# FPGA_APU_V3.net
KiCad netlist of a schematic drawn in EAGLE
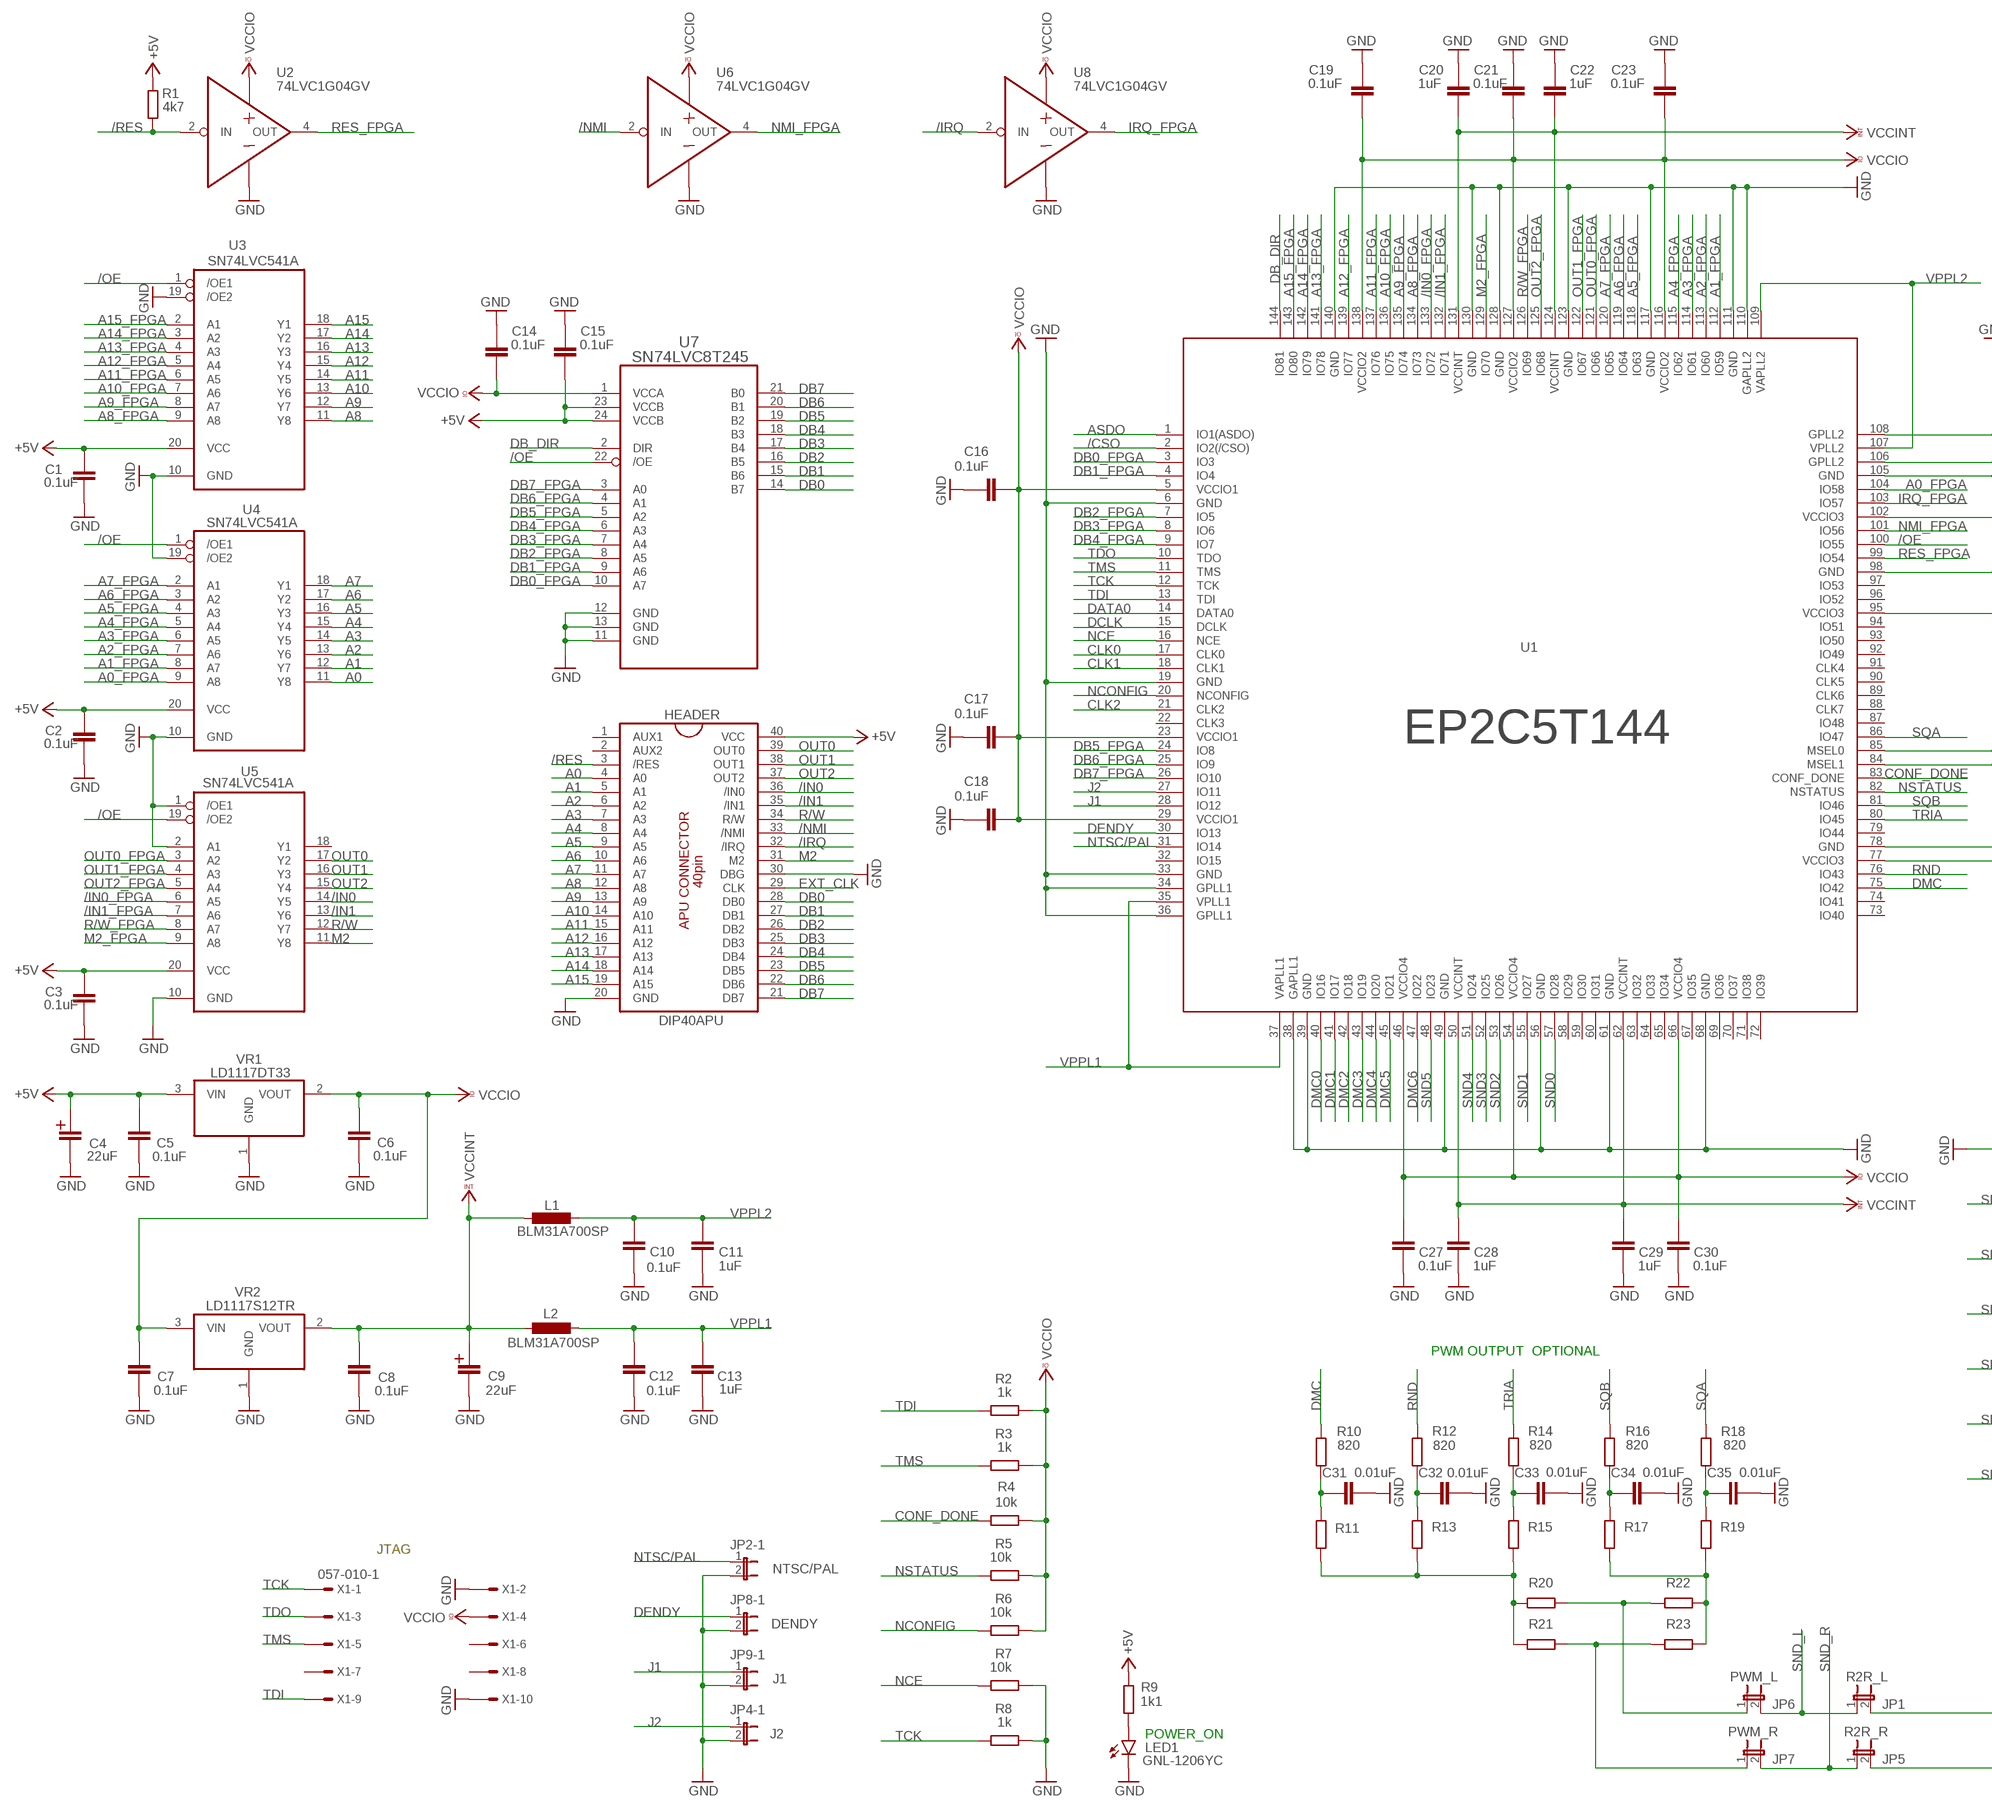
[diagram p0: schematic, sheet 1, part 1 of 2]
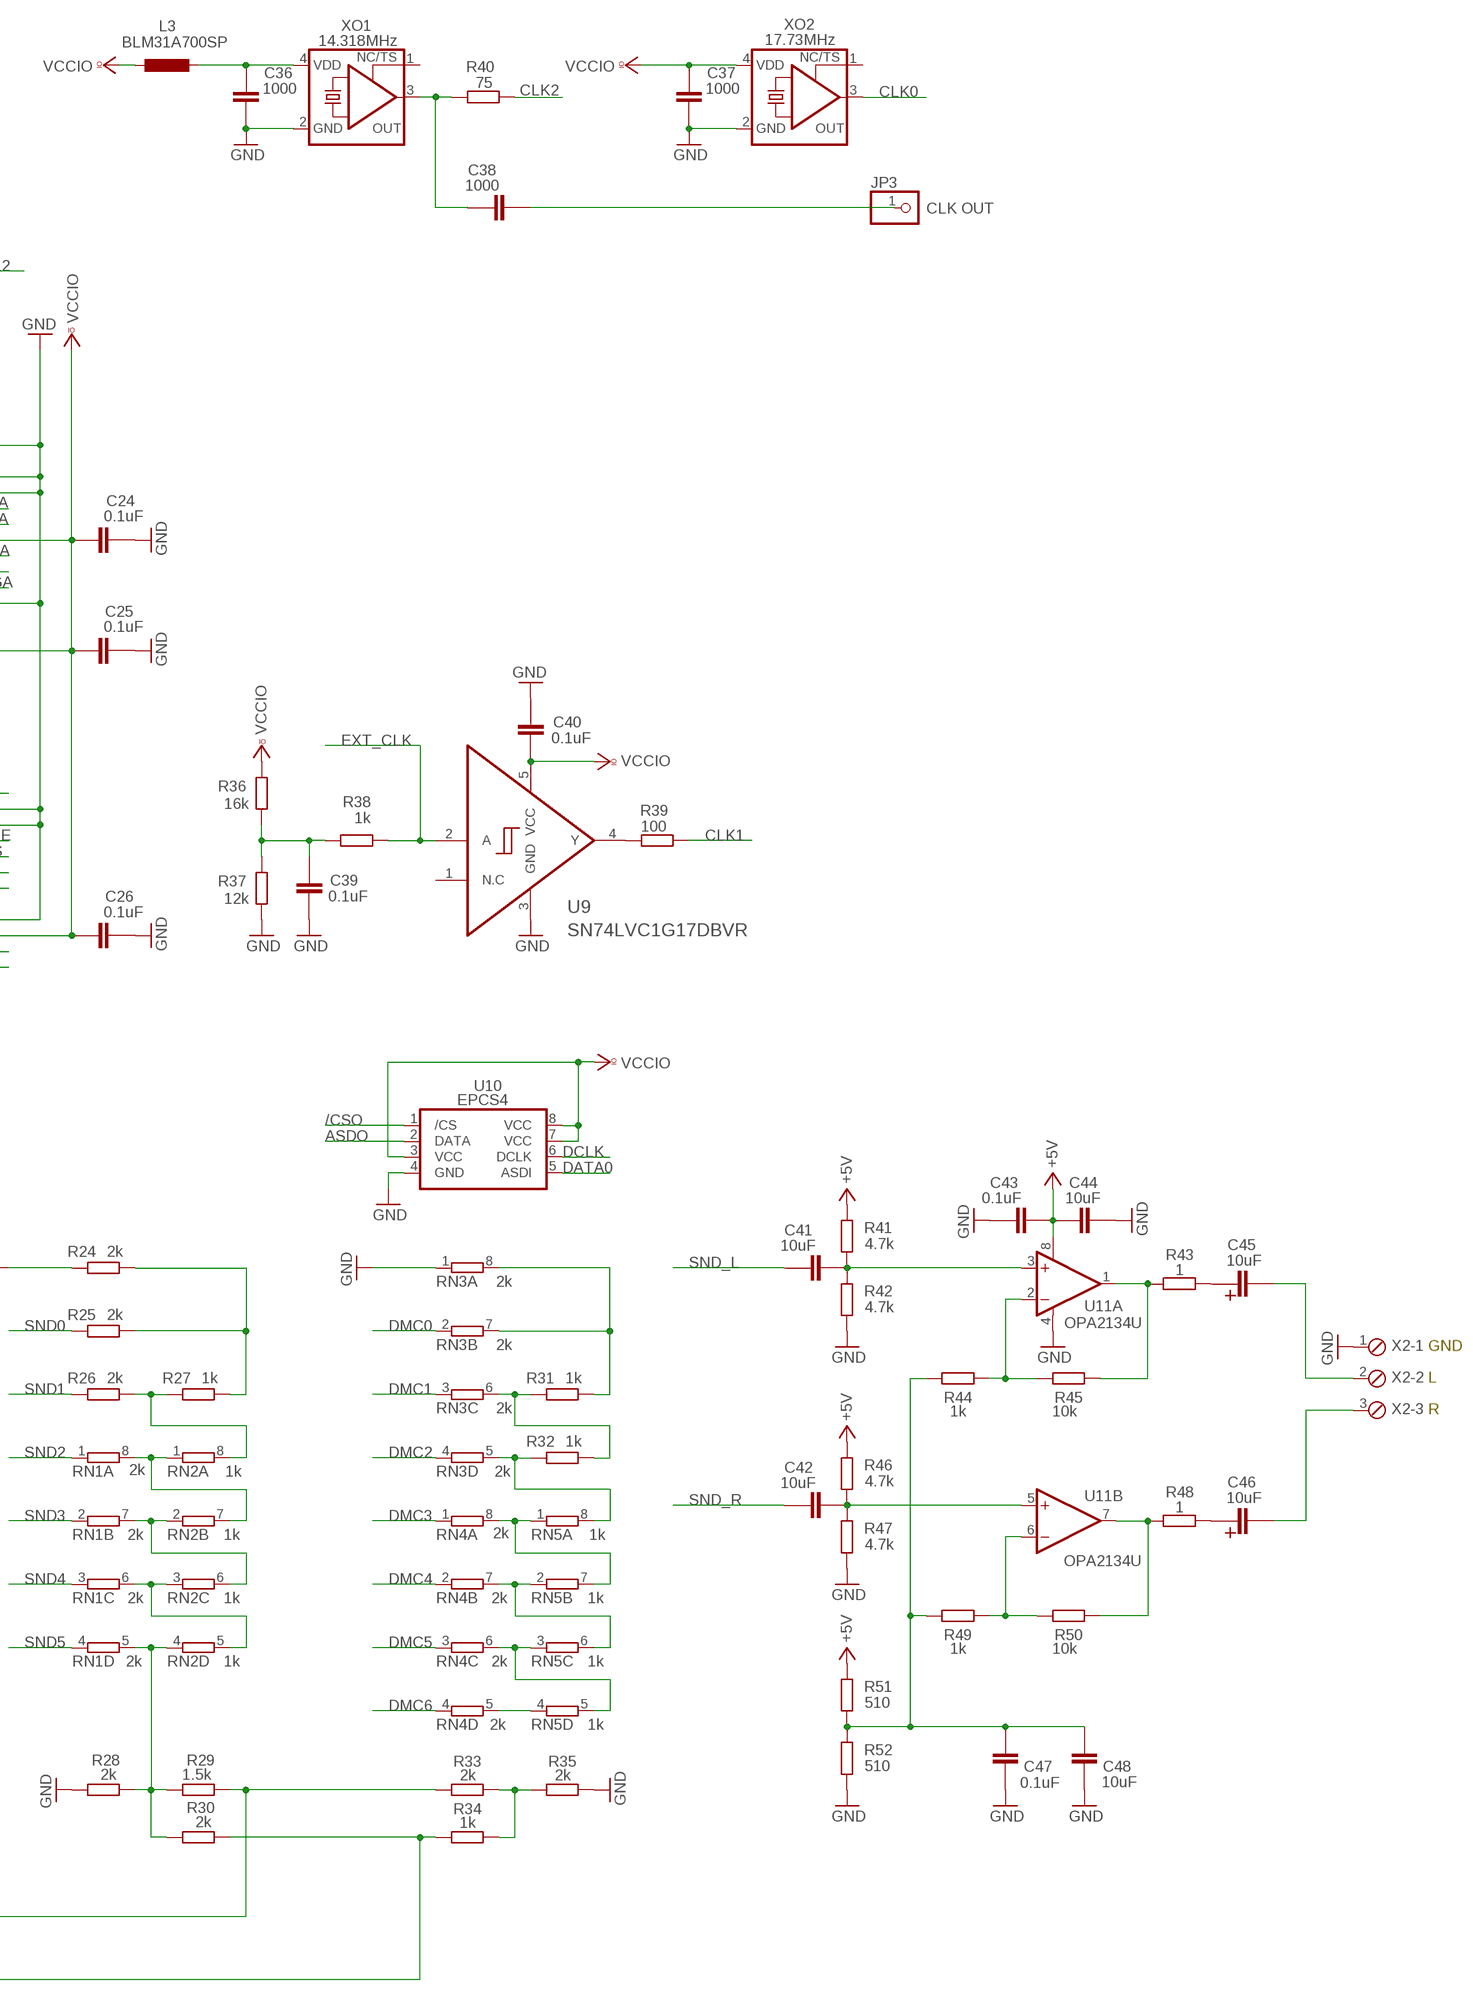
[diagram p1: schematic, sheet 1, part 2 of 2]

(export (version "E")
  (design (tool "Eeschema 10.0.6"))
  (components
    (comp (ref "C1")
      (value "0.1uF")
      (footprint "eagle-import:C0805")
      (libsource (lib "eagle-import") (part "C-EUC0805"))
    )
    (comp (ref "C2")
      (value "0.1uF")
      (footprint "eagle-import:C0805")
      (libsource (lib "eagle-import") (part "C-EUC0805"))
    )
    (comp (ref "C3")
      (value "0.1uF")
      (footprint "eagle-import:C0805")
      (libsource (lib "eagle-import") (part "C-EUC0805"))
    )
    (comp (ref "C4")
      (value "22uF")
      (footprint "eagle-import:153CLV-0505")
      (libsource (lib "eagle-import") (part "CPOL-EU153CLV-0505"))
    )
    (comp (ref "C5")
      (value "0.1uF")
      (footprint "eagle-import:C0805")
      (libsource (lib "eagle-import") (part "C-EUC0805"))
    )
    (comp (ref "C6")
      (value "0.1uF")
      (footprint "eagle-import:C0805")
      (libsource (lib "eagle-import") (part "C-EUC0805"))
    )
    (comp (ref "C7")
      (value "0.1uF")
      (footprint "eagle-import:C0805")
      (libsource (lib "eagle-import") (part "C-EUC0805"))
    )
    (comp (ref "C8")
      (value "0.1uF")
      (footprint "eagle-import:C0805")
      (libsource (lib "eagle-import") (part "C-EUC0805"))
    )
    (comp (ref "C9")
      (value "22uF")
      (footprint "eagle-import:153CLV-0505")
      (libsource (lib "eagle-import") (part "CPOL-EU153CLV-0505"))
    )
    (comp (ref "C10")
      (value "0.1uF")
      (footprint "eagle-import:C0805")
      (libsource (lib "eagle-import") (part "C-EUC0805"))
    )
    (comp (ref "C11")
      (value "1uF")
      (footprint "eagle-import:C0805")
      (libsource (lib "eagle-import") (part "C-EUC0805"))
    )
    (comp (ref "C12")
      (value "0.1uF")
      (footprint "eagle-import:C0805")
      (libsource (lib "eagle-import") (part "C-EUC0805"))
    )
    (comp (ref "C13")
      (value "1uF")
      (footprint "eagle-import:C0805")
      (libsource (lib "eagle-import") (part "C-EUC0805"))
    )
    (comp (ref "C14")
      (value "0.1uF")
      (footprint "eagle-import:C0805")
      (libsource (lib "eagle-import") (part "C-EUC0805"))
    )
    (comp (ref "C15")
      (value "0.1uF")
      (footprint "eagle-import:C0805")
      (libsource (lib "eagle-import") (part "C-EUC0805"))
    )
    (comp (ref "C16")
      (value "0.1uF")
      (footprint "eagle-import:C0805")
      (libsource (lib "eagle-import") (part "C-EUC0805"))
    )
    (comp (ref "C17")
      (value "0.1uF")
      (footprint "eagle-import:C0805")
      (libsource (lib "eagle-import") (part "C-EUC0805"))
    )
    (comp (ref "C18")
      (value "0.1uF")
      (footprint "eagle-import:C0805")
      (libsource (lib "eagle-import") (part "C-EUC0805"))
    )
    (comp (ref "C19")
      (value "0.1uF")
      (footprint "eagle-import:C0805")
      (libsource (lib "eagle-import") (part "C-EUC0805"))
    )
    (comp (ref "C20")
      (value "1uF")
      (footprint "eagle-import:C0805")
      (libsource (lib "eagle-import") (part "C-EUC0805"))
    )
    (comp (ref "C21")
      (value "0.1uF")
      (footprint "eagle-import:C0805")
      (libsource (lib "eagle-import") (part "C-EUC0805"))
    )
    (comp (ref "C22")
      (value "1uF")
      (footprint "eagle-import:C0805")
      (libsource (lib "eagle-import") (part "C-EUC0805"))
    )
    (comp (ref "C23")
      (value "0.1uF")
      (footprint "eagle-import:C0805")
      (libsource (lib "eagle-import") (part "C-EUC0805"))
    )
    (comp (ref "C24")
      (value "0.1uF")
      (footprint "eagle-import:C0805")
      (libsource (lib "eagle-import") (part "C-EUC0805"))
    )
    (comp (ref "C25")
      (value "0.1uF")
      (footprint "eagle-import:C0805")
      (libsource (lib "eagle-import") (part "C-EUC0805"))
    )
    (comp (ref "C26")
      (value "0.1uF")
      (footprint "eagle-import:C0805")
      (libsource (lib "eagle-import") (part "C-EUC0805"))
    )
    (comp (ref "C27")
      (value "0.1uF")
      (footprint "eagle-import:C0805")
      (libsource (lib "eagle-import") (part "C-EUC0805"))
    )
    (comp (ref "C28")
      (value "1uF")
      (footprint "eagle-import:C0805")
      (libsource (lib "eagle-import") (part "C-EUC0805"))
    )
    (comp (ref "C29")
      (value "1uF")
      (footprint "eagle-import:C0805")
      (libsource (lib "eagle-import") (part "C-EUC0805"))
    )
    (comp (ref "C30")
      (value "0.1uF")
      (footprint "eagle-import:C0805")
      (libsource (lib "eagle-import") (part "C-EUC0805"))
    )
    (comp (ref "C31")
      (value "0.01uF")
      (footprint "eagle-import:C0805")
      (libsource (lib "eagle-import") (part "C-EUC0805"))
    )
    (comp (ref "C32")
      (value "0.01uF")
      (footprint "eagle-import:C0805")
      (libsource (lib "eagle-import") (part "C-EUC0805"))
    )
    (comp (ref "C33")
      (value "0.01uF")
      (footprint "eagle-import:C0805")
      (libsource (lib "eagle-import") (part "C-EUC0805"))
    )
    (comp (ref "C34")
      (value "0.01uF")
      (footprint "eagle-import:C0805")
      (libsource (lib "eagle-import") (part "C-EUC0805"))
    )
    (comp (ref "C35")
      (value "0.01uF")
      (footprint "eagle-import:C0805")
      (libsource (lib "eagle-import") (part "C-EUC0805"))
    )
    (comp (ref "C36")
      (value "1000")
      (footprint "eagle-import:C0805")
      (libsource (lib "eagle-import") (part "C-EUC0805"))
    )
    (comp (ref "C37")
      (value "1000")
      (footprint "eagle-import:C0805")
      (libsource (lib "eagle-import") (part "C-EUC0805"))
    )
    (comp (ref "C38")
      (value "1000")
      (footprint "eagle-import:C0805")
      (libsource (lib "eagle-import") (part "C-EUC0805"))
    )
    (comp (ref "C39")
      (value "0.1uF")
      (footprint "eagle-import:C0603")
      (libsource (lib "eagle-import") (part "C-EUC0603"))
    )
    (comp (ref "C40")
      (value "0.1uF")
      (footprint "eagle-import:C0603")
      (libsource (lib "eagle-import") (part "C-EUC0603"))
    )
    (comp (ref "C41")
      (value "10uF")
      (footprint "eagle-import:C0805")
      (libsource (lib "eagle-import") (part "C-EUC0805"))
    )
    (comp (ref "C42")
      (value "10uF")
      (footprint "eagle-import:C0805")
      (libsource (lib "eagle-import") (part "C-EUC0805"))
    )
    (comp (ref "C43")
      (value "0.1uF")
      (footprint "eagle-import:C0805")
      (libsource (lib "eagle-import") (part "C-EUC0805"))
    )
    (comp (ref "C44")
      (value "10uF")
      (footprint "eagle-import:C0805")
      (libsource (lib "eagle-import") (part "C-EUC0805"))
    )
    (comp (ref "C45")
      (value "10uF")
      (footprint "eagle-import:153CLV-0505")
      (libsource (lib "eagle-import") (part "CPOL-EU153CLV-0505"))
    )
    (comp (ref "C46")
      (value "10uF")
      (footprint "eagle-import:153CLV-0505")
      (libsource (lib "eagle-import") (part "CPOL-EU153CLV-0505"))
    )
    (comp (ref "C47")
      (value "0.1uF")
      (footprint "eagle-import:C0805")
      (libsource (lib "eagle-import") (part "C-EUC0805"))
    )
    (comp (ref "C48")
      (value "10uF")
      (footprint "eagle-import:C0805")
      (libsource (lib "eagle-import") (part "C-EUC0805"))
    )
    (comp (ref "HEADER")
      (value "DIP40APU")
      (footprint "eagle-import:DIP-40")
      (libsource (lib "eagle-import") (part "DIP40APU"))
    )
    (comp (ref "JP1")
      (value "R2R_L")
      (footprint "eagle-import:JP1")
      (libsource (lib "eagle-import") (part "JP1E"))
    )
    (comp (ref "JP2")
      (value "NTSC/PAL")
      (footprint "eagle-import:JP4Q")
      (libsource (lib "eagle-import") (part "JP4QE"))
    )
    (comp (ref "JP3")
      (value "CLK OUT")
      (footprint "eagle-import:1X01")
      (libsource (lib "eagle-import") (part "PINHD-1X1"))
    )
    (comp (ref "JP4")
      (value "J2")
      (footprint "eagle-import:JP4Q")
      (libsource (lib "eagle-import") (part "JP4QE"))
    )
    (comp (ref "JP5")
      (value "R2R_R")
      (footprint "eagle-import:JP1")
      (libsource (lib "eagle-import") (part "JP1E"))
    )
    (comp (ref "JP6")
      (value "PWM_L")
      (footprint "eagle-import:JP1")
      (libsource (lib "eagle-import") (part "JP1E"))
    )
    (comp (ref "JP7")
      (value "PWM_R")
      (footprint "eagle-import:JP1")
      (libsource (lib "eagle-import") (part "JP1E"))
    )
    (comp (ref "JP8")
      (value "DENDY")
      (footprint "eagle-import:JP4Q")
      (libsource (lib "eagle-import") (part "JP4QE"))
    )
    (comp (ref "JP9")
      (value "J1")
      (footprint "eagle-import:JP4Q")
      (libsource (lib "eagle-import") (part "JP4QE"))
    )
    (comp (ref "L1")
      (value "BLM31A700SP")
      (footprint "eagle-import:L2012C")
      (libsource (lib "eagle-import") (part "L-EUL2012C"))
    )
    (comp (ref "L2")
      (value "BLM31A700SP")
      (footprint "eagle-import:L2012C")
      (libsource (lib "eagle-import") (part "L-EUL2012C"))
    )
    (comp (ref "L3")
      (value "BLM31A700SP")
      (footprint "eagle-import:L2012C")
      (libsource (lib "eagle-import") (part "L-EUL2012C"))
    )
    (comp (ref "LED1")
      (value "GNL-1206YC")
      (footprint "eagle-import:SMARTLED-TTW")
      (libsource (lib "eagle-import") (part "LED"))
    )
    (comp (ref "R1")
      (value "4k7")
      (footprint "eagle-import:R0805")
      (libsource (lib "eagle-import") (part "R-EU_R0805"))
    )
    (comp (ref "R2")
      (value "1k")
      (footprint "eagle-import:R0805")
      (libsource (lib "eagle-import") (part "R-EU_R0805"))
    )
    (comp (ref "R3")
      (value "1k")
      (footprint "eagle-import:R0805")
      (libsource (lib "eagle-import") (part "R-EU_R0805"))
    )
    (comp (ref "R4")
      (value "10k")
      (footprint "eagle-import:R0805")
      (libsource (lib "eagle-import") (part "R-EU_R0805"))
    )
    (comp (ref "R5")
      (value "10k")
      (footprint "eagle-import:R0805")
      (libsource (lib "eagle-import") (part "R-EU_R0805"))
    )
    (comp (ref "R6")
      (value "10k")
      (footprint "eagle-import:R0805")
      (libsource (lib "eagle-import") (part "R-EU_R0805"))
    )
    (comp (ref "R7")
      (value "10k")
      (footprint "eagle-import:R0805")
      (libsource (lib "eagle-import") (part "R-EU_R0805"))
    )
    (comp (ref "R8")
      (value "1k")
      (footprint "eagle-import:R0805")
      (libsource (lib "eagle-import") (part "R-EU_R0805"))
    )
    (comp (ref "R9")
      (value "1k1")
      (footprint "eagle-import:R0805")
      (libsource (lib "eagle-import") (part "R-EU_R0805"))
    )
    (comp (ref "R10")
      (value "820")
      (footprint "eagle-import:R0805")
      (libsource (lib "eagle-import") (part "R-EU_R0805"))
    )
    (comp (ref "R11")
      (value "R-EU_R0805")
      (footprint "eagle-import:R0805")
      (libsource (lib "eagle-import") (part "R-EU_R0805"))
    )
    (comp (ref "R12")
      (value "820")
      (footprint "eagle-import:R0805")
      (libsource (lib "eagle-import") (part "R-EU_R0805"))
    )
    (comp (ref "R13")
      (value "R-EU_R0805")
      (footprint "eagle-import:R0805")
      (libsource (lib "eagle-import") (part "R-EU_R0805"))
    )
    (comp (ref "R14")
      (value "820")
      (footprint "eagle-import:R0805")
      (libsource (lib "eagle-import") (part "R-EU_R0805"))
    )
    (comp (ref "R15")
      (value "R-EU_R0805")
      (footprint "eagle-import:R0805")
      (libsource (lib "eagle-import") (part "R-EU_R0805"))
    )
    (comp (ref "R16")
      (value "820")
      (footprint "eagle-import:R0805")
      (libsource (lib "eagle-import") (part "R-EU_R0805"))
    )
    (comp (ref "R17")
      (value "R-EU_R0805")
      (footprint "eagle-import:R0805")
      (libsource (lib "eagle-import") (part "R-EU_R0805"))
    )
    (comp (ref "R18")
      (value "820")
      (footprint "eagle-import:R0805")
      (libsource (lib "eagle-import") (part "R-EU_R0805"))
    )
    (comp (ref "R19")
      (value "R-EU_R0805")
      (footprint "eagle-import:R0805")
      (libsource (lib "eagle-import") (part "R-EU_R0805"))
    )
    (comp (ref "R20")
      (value "R-EU_R0805")
      (footprint "eagle-import:R0805")
      (libsource (lib "eagle-import") (part "R-EU_R0805"))
    )
    (comp (ref "R21")
      (value "R-EU_R0805")
      (footprint "eagle-import:R0805")
      (libsource (lib "eagle-import") (part "R-EU_R0805"))
    )
    (comp (ref "R22")
      (value "R-EU_R0805")
      (footprint "eagle-import:R0805")
      (libsource (lib "eagle-import") (part "R-EU_R0805"))
    )
    (comp (ref "R23")
      (value "R-EU_R0805")
      (footprint "eagle-import:R0805")
      (libsource (lib "eagle-import") (part "R-EU_R0805"))
    )
    (comp (ref "R24")
      (value "2k")
      (footprint "eagle-import:R0805")
      (libsource (lib "eagle-import") (part "R-EU_R0805"))
    )
    (comp (ref "R25")
      (value "2k")
      (footprint "eagle-import:R0805")
      (libsource (lib "eagle-import") (part "R-EU_R0805"))
    )
    (comp (ref "R26")
      (value "2k")
      (footprint "eagle-import:R0805")
      (libsource (lib "eagle-import") (part "R-EU_R0805"))
    )
    (comp (ref "R27")
      (value "1k")
      (footprint "eagle-import:R0805")
      (libsource (lib "eagle-import") (part "R-EU_R0805"))
    )
    (comp (ref "R28")
      (value "2k")
      (footprint "eagle-import:R0805")
      (libsource (lib "eagle-import") (part "R-EU_R0805"))
    )
    (comp (ref "R29")
      (value "1.5k")
      (footprint "eagle-import:R0805")
      (libsource (lib "eagle-import") (part "R-EU_R0805"))
    )
    (comp (ref "R30")
      (value "2k")
      (footprint "eagle-import:R0805")
      (libsource (lib "eagle-import") (part "R-EU_R0805"))
    )
    (comp (ref "R31")
      (value "1k")
      (footprint "eagle-import:R0805")
      (libsource (lib "eagle-import") (part "R-EU_R0805"))
    )
    (comp (ref "R32")
      (value "1k")
      (footprint "eagle-import:R0805")
      (libsource (lib "eagle-import") (part "R-EU_R0805"))
    )
    (comp (ref "R33")
      (value "2k")
      (footprint "eagle-import:R0805")
      (libsource (lib "eagle-import") (part "R-EU_R0805"))
    )
    (comp (ref "R34")
      (value "1k")
      (footprint "eagle-import:R0805")
      (libsource (lib "eagle-import") (part "R-EU_R0805"))
    )
    (comp (ref "R35")
      (value "2k")
      (footprint "eagle-import:R0805")
      (libsource (lib "eagle-import") (part "R-EU_R0805"))
    )
    (comp (ref "R36")
      (value "16k")
      (footprint "eagle-import:R0805")
      (libsource (lib "eagle-import") (part "R-EU_R0805"))
    )
    (comp (ref "R37")
      (value "12k")
      (footprint "eagle-import:R0805")
      (libsource (lib "eagle-import") (part "R-EU_R0805"))
    )
    (comp (ref "R38")
      (value "1k")
      (footprint "eagle-import:R0805")
      (libsource (lib "eagle-import") (part "R-EU_R0805"))
    )
    (comp (ref "R39")
      (value "100")
      (footprint "eagle-import:R0805")
      (libsource (lib "eagle-import") (part "R-EU_R0805"))
    )
    (comp (ref "R40")
      (value "75")
      (footprint "eagle-import:R0805")
      (libsource (lib "eagle-import") (part "R-EU_R0805"))
    )
    (comp (ref "R41")
      (value "4.7k")
      (footprint "eagle-import:R0805")
      (libsource (lib "eagle-import") (part "R-EU_R0805"))
    )
    (comp (ref "R42")
      (value "4.7k")
      (footprint "eagle-import:R0805")
      (libsource (lib "eagle-import") (part "R-EU_R0805"))
    )
    (comp (ref "R43")
      (value "1")
      (footprint "eagle-import:R0805")
      (libsource (lib "eagle-import") (part "R-EU_R0805"))
    )
    (comp (ref "R44")
      (value "1k")
      (footprint "eagle-import:R0805")
      (libsource (lib "eagle-import") (part "R-EU_R0805"))
    )
    (comp (ref "R45")
      (value "10k")
      (footprint "eagle-import:R0805")
      (libsource (lib "eagle-import") (part "R-EU_R0805"))
    )
    (comp (ref "R46")
      (value "4.7k")
      (footprint "eagle-import:R0805")
      (libsource (lib "eagle-import") (part "R-EU_R0805"))
    )
    (comp (ref "R47")
      (value "4.7k")
      (footprint "eagle-import:R0805")
      (libsource (lib "eagle-import") (part "R-EU_R0805"))
    )
    (comp (ref "R48")
      (value "1")
      (footprint "eagle-import:R0805")
      (libsource (lib "eagle-import") (part "R-EU_R0805"))
    )
    (comp (ref "R49")
      (value "1k")
      (footprint "eagle-import:R0805")
      (libsource (lib "eagle-import") (part "R-EU_R0805"))
    )
    (comp (ref "R50")
      (value "10k")
      (footprint "eagle-import:R0805")
      (libsource (lib "eagle-import") (part "R-EU_R0805"))
    )
    (comp (ref "R51")
      (value "510")
      (footprint "eagle-import:R0805")
      (libsource (lib "eagle-import") (part "R-EU_R0805"))
    )
    (comp (ref "R52")
      (value "510")
      (footprint "eagle-import:R0805")
      (libsource (lib "eagle-import") (part "R-EU_R0805"))
    )
    (comp (ref "RN1")
      (value "2k")
      (footprint "eagle-import:0603-ARC")
      (libsource (lib "eagle-import") (part "4R-N0603-ARC"))
    )
    (comp (ref "RN2")
      (value "1k")
      (footprint "eagle-import:0603-ARC")
      (libsource (lib "eagle-import") (part "4R-N0603-ARC"))
    )
    (comp (ref "RN3")
      (value "2k")
      (footprint "eagle-import:0603-ARC")
      (libsource (lib "eagle-import") (part "4R-N0603-ARC"))
    )
    (comp (ref "RN4")
      (value "2k")
      (footprint "eagle-import:0603-ARC")
      (libsource (lib "eagle-import") (part "4R-N0603-ARC"))
    )
    (comp (ref "RN5")
      (value "1k")
      (footprint "eagle-import:0603-ARC")
      (libsource (lib "eagle-import") (part "4R-N0603-ARC"))
    )
    (comp (ref "U1")
      (value "EP2C5T144")
      (footprint "eagle-import:TQFP144")
      (fields (field (name "MPN") "EP2C5T144C8N"))
      (libsource (lib "eagle-import") (part "EP2C5T144"))
    )
    (comp (ref "U2")
      (value "74LVC1G04GV")
      (footprint "eagle-import:SOT95P275X110-5N")
      (libsource (lib "eagle-import") (part "74LVC1G04GV"))
    )
    (comp (ref "U3")
      (value "SN74LVC541A")
      (footprint "eagle-import:TSOP20")
      (libsource (lib "eagle-import") (part "SN74LVC541A"))
    )
    (comp (ref "U4")
      (value "SN74LVC541A")
      (footprint "eagle-import:TSOP20")
      (libsource (lib "eagle-import") (part "SN74LVC541A"))
    )
    (comp (ref "U5")
      (value "SN74LVC541A")
      (footprint "eagle-import:TSOP20")
      (libsource (lib "eagle-import") (part "SN74LVC541A"))
    )
    (comp (ref "U6")
      (value "74LVC1G04GV")
      (footprint "eagle-import:SOT95P275X110-5N")
      (libsource (lib "eagle-import") (part "74LVC1G04GV"))
    )
    (comp (ref "U7")
      (value "SN74LVC8T245")
      (footprint "eagle-import:SOP65P640X110-24N")
      (libsource (lib "eagle-import") (part "SN74LVC8T245"))
    )
    (comp (ref "U8")
      (value "74LVC1G04GV")
      (footprint "eagle-import:SOT95P275X110-5N")
      (libsource (lib "eagle-import") (part "74LVC1G04GV"))
    )
    (comp (ref "U9")
      (value "SN74LVC1G17DBVR")
      (footprint "eagle-import:SOT95P280X145-5N")
      (libsource (lib "eagle-import") (part "SN74LVC1G17DBVR"))
    )
    (comp (ref "U10")
      (value "EPCS4")
      (footprint "eagle-import:SO08")
      (libsource (lib "eagle-import") (part "EPCS4"))
    )
    (comp (ref "U11")
      (value "OPA2134U")
      (footprint "eagle-import:SO08")
      (fields (field (name "MF") "TEXAS INSTRUMENTS") (field (name "MPN") "OPA2134UA"))
      (libsource (lib "eagle-import") (part "OPA2134U"))
    )
    (comp (ref "VR1")
      (value "LD1117DT33")
      (footprint "eagle-import:DPAK456P1010X240-3N")
      (fields (field (name "MANUFACTURER") "STMicroelectronics"))
      (libsource (lib "eagle-import") (part "LD1117DT33"))
    )
    (comp (ref "VR2")
      (value "LD1117S12TR")
      (footprint "eagle-import:SOT-223-3")
      (libsource (lib "eagle-import") (part "LD1117S12TR"))
    )
    (comp (ref "X1")
      (value "057-010-1")
      (footprint "eagle-import:057-010-1")
      (libsource (lib "eagle-import") (part "057-010-1"))
    )
    (comp (ref "X2")
      (value "OUT")
      (footprint "eagle-import:7POL254")
      (libsource (lib "eagle-import") (part "MPT7"))
    )
    (comp (ref "XO1")
      (value "14.318MHz")
      (footprint "eagle-import:7.0X5.08_KXO-(V)97")
      (libsource (lib "eagle-import") (part "KXO-PXO/XO-V97"))
    )
    (comp (ref "XO2")
      (value "17.73MHz")
      (footprint "eagle-import:2.5X2.0_KXO-V95")
      (libsource (lib "eagle-import") (part "KXO-PXO/XO-V95"))
    )
  )
  (nets
    (net (code "1") (name "+5V") (class "Default")
      (node (ref "C1") (pin "1") (pinfunction "1_1") (pintype "passive"))
      (node (ref "C15") (pin "2") (pinfunction "2_2") (pintype "passive"))
      (node (ref "C2") (pin "1") (pinfunction "1_1") (pintype "passive"))
      (node (ref "C3") (pin "1") (pinfunction "1_1") (pintype "passive"))
      (node (ref "C4") (pin "+") (pinfunction "+_+") (pintype "passive"))
      (node (ref "C43") (pin "2") (pinfunction "2_2") (pintype "passive"))
      (node (ref "C44") (pin "1") (pinfunction "1_1") (pintype "passive"))
      (node (ref "C5") (pin "1") (pinfunction "1_1") (pintype "passive"))
      (node (ref "HEADER") (pin "40") (pinfunction "VCC_40") (pintype "power_in"))
      (node (ref "R1") (pin "1") (pinfunction "1_1") (pintype "passive"))
      (node (ref "R41") (pin "1") (pinfunction "1_1") (pintype "passive"))
      (node (ref "R46") (pin "1") (pinfunction "1_1") (pintype "passive"))
      (node (ref "R51") (pin "1") (pinfunction "1_1") (pintype "passive"))
      (node (ref "R9") (pin "2") (pinfunction "2_2") (pintype "passive"))
      (node (ref "U11") (pin "8") (pinfunction "V+_8") (pintype "power_in"))
      (node (ref "U3") (pin "20") (pinfunction "VCC_20") (pintype "power_in"))
      (node (ref "U4") (pin "20") (pinfunction "VCC_20") (pintype "power_in"))
      (node (ref "U5") (pin "20") (pinfunction "VCC_20") (pintype "power_in"))
      (node (ref "U7") (pin "23") (pinfunction "VCCB_23") (pintype "power_in"))
      (node (ref "U7") (pin "24") (pinfunction "VCCB_24") (pintype "power_in"))
      (node (ref "VR1") (pin "3") (pinfunction "VIN_3") (pintype "power_in"))
    )
    (net (code "2") (name "/A0") (class "Default")
      (node (ref "HEADER") (pin "4") (pinfunction "A0_4") (pintype "input"))
      (node (ref "U4") (pin "11") (pinfunction "Y8_11") (pintype "output"))
    )
    (net (code "3") (name "/A0_FPGA") (class "Default")
      (node (ref "U1") (pin "104") (pinfunction "IO58_104") (pintype "bidirectional"))
      (node (ref "U4") (pin "9") (pinfunction "A8_9") (pintype "input"))
    )
    (net (code "4") (name "/A1") (class "Default")
      (node (ref "HEADER") (pin "5") (pinfunction "A1_5") (pintype "input"))
      (node (ref "U4") (pin "12") (pinfunction "Y7_12") (pintype "output"))
    )
    (net (code "5") (name "/A1_FPGA") (class "Default")
      (node (ref "U1") (pin "112") (pinfunction "IO59_112") (pintype "bidirectional"))
      (node (ref "U4") (pin "8") (pinfunction "A7_8") (pintype "input"))
    )
    (net (code "6") (name "/A2") (class "Default")
      (node (ref "HEADER") (pin "6") (pinfunction "A2_6") (pintype "input"))
      (node (ref "U4") (pin "13") (pinfunction "Y6_13") (pintype "output"))
    )
    (net (code "7") (name "/A2_FPGA") (class "Default")
      (node (ref "U1") (pin "113") (pinfunction "IO60_113") (pintype "bidirectional"))
      (node (ref "U4") (pin "7") (pinfunction "A6_7") (pintype "input"))
    )
    (net (code "8") (name "/A3") (class "Default")
      (node (ref "HEADER") (pin "7") (pinfunction "A3_7") (pintype "input"))
      (node (ref "U4") (pin "14") (pinfunction "Y5_14") (pintype "output"))
    )
    (net (code "9") (name "/A3_FPGA") (class "Default")
      (node (ref "U1") (pin "114") (pinfunction "IO61_114") (pintype "bidirectional"))
      (node (ref "U4") (pin "6") (pinfunction "A5_6") (pintype "input"))
    )
    (net (code "10") (name "/A4") (class "Default")
      (node (ref "HEADER") (pin "8") (pinfunction "A4_8") (pintype "input"))
      (node (ref "U4") (pin "15") (pinfunction "Y4_15") (pintype "output"))
    )
    (net (code "11") (name "/A4_FPGA") (class "Default")
      (node (ref "U1") (pin "115") (pinfunction "IO62_115") (pintype "bidirectional"))
      (node (ref "U4") (pin "5") (pinfunction "A4_5") (pintype "input"))
    )
    (net (code "12") (name "/A5") (class "Default")
      (node (ref "HEADER") (pin "9") (pinfunction "A5_9") (pintype "input"))
      (node (ref "U4") (pin "16") (pinfunction "Y3_16") (pintype "output"))
    )
    (net (code "13") (name "/A5_FPGA") (class "Default")
      (node (ref "U1") (pin "118") (pinfunction "IO63_118") (pintype "bidirectional"))
      (node (ref "U4") (pin "4") (pinfunction "A3_4") (pintype "input"))
    )
    (net (code "14") (name "/A6") (class "Default")
      (node (ref "HEADER") (pin "10") (pinfunction "A6_10") (pintype "input"))
      (node (ref "U4") (pin "17") (pinfunction "Y2_17") (pintype "output"))
    )
    (net (code "15") (name "/A6_FPGA") (class "Default")
      (node (ref "U1") (pin "119") (pinfunction "IO64_119") (pintype "bidirectional"))
      (node (ref "U4") (pin "3") (pinfunction "A2_3") (pintype "input"))
    )
    (net (code "16") (name "/A7") (class "Default")
      (node (ref "HEADER") (pin "11") (pinfunction "A7_11") (pintype "input"))
      (node (ref "U4") (pin "18") (pinfunction "Y1_18") (pintype "output"))
    )
    (net (code "17") (name "/A7_FPGA") (class "Default")
      (node (ref "U1") (pin "120") (pinfunction "IO65_120") (pintype "bidirectional"))
      (node (ref "U4") (pin "2") (pinfunction "A1_2") (pintype "input"))
    )
    (net (code "18") (name "/A8") (class "Default")
      (node (ref "HEADER") (pin "12") (pinfunction "A8_12") (pintype "input"))
      (node (ref "U3") (pin "11") (pinfunction "Y8_11") (pintype "output"))
    )
    (net (code "19") (name "/A8_FPGA") (class "Default")
      (node (ref "U1") (pin "134") (pinfunction "IO73_134") (pintype "bidirectional"))
      (node (ref "U3") (pin "9") (pinfunction "A8_9") (pintype "input"))
    )
    (net (code "20") (name "/A9") (class "Default")
      (node (ref "HEADER") (pin "13") (pinfunction "A9_13") (pintype "input"))
      (node (ref "U3") (pin "12") (pinfunction "Y7_12") (pintype "output"))
    )
    (net (code "21") (name "/A9_FPGA") (class "Default")
      (node (ref "U1") (pin "135") (pinfunction "IO74_135") (pintype "bidirectional"))
      (node (ref "U3") (pin "8") (pinfunction "A7_8") (pintype "input"))
    )
    (net (code "22") (name "/A10") (class "Default")
      (node (ref "HEADER") (pin "14") (pinfunction "A10_14") (pintype "input"))
      (node (ref "U3") (pin "13") (pinfunction "Y6_13") (pintype "output"))
    )
    (net (code "23") (name "/A10_FPGA") (class "Default")
      (node (ref "U1") (pin "136") (pinfunction "IO75_136") (pintype "bidirectional"))
      (node (ref "U3") (pin "7") (pinfunction "A6_7") (pintype "input"))
    )
    (net (code "24") (name "/A11") (class "Default")
      (node (ref "HEADER") (pin "15") (pinfunction "A11_15") (pintype "input"))
      (node (ref "U3") (pin "14") (pinfunction "Y5_14") (pintype "output"))
    )
    (net (code "25") (name "/A11_FPGA") (class "Default")
      (node (ref "U1") (pin "137") (pinfunction "IO76_137") (pintype "bidirectional"))
      (node (ref "U3") (pin "6") (pinfunction "A5_6") (pintype "input"))
    )
    (net (code "26") (name "/A12") (class "Default")
      (node (ref "HEADER") (pin "16") (pinfunction "A12_16") (pintype "input"))
      (node (ref "U3") (pin "15") (pinfunction "Y4_15") (pintype "output"))
    )
    (net (code "27") (name "/A12_FPGA") (class "Default")
      (node (ref "U1") (pin "139") (pinfunction "IO77_139") (pintype "bidirectional"))
      (node (ref "U3") (pin "5") (pinfunction "A4_5") (pintype "input"))
    )
    (net (code "28") (name "/A13") (class "Default")
      (node (ref "HEADER") (pin "17") (pinfunction "A13_17") (pintype "input"))
      (node (ref "U3") (pin "16") (pinfunction "Y3_16") (pintype "output"))
    )
    (net (code "29") (name "/A13_FPGA") (class "Default")
      (node (ref "U1") (pin "141") (pinfunction "IO78_141") (pintype "bidirectional"))
      (node (ref "U3") (pin "4") (pinfunction "A3_4") (pintype "input"))
    )
    (net (code "30") (name "/A14") (class "Default")
      (node (ref "HEADER") (pin "18") (pinfunction "A14_18") (pintype "input"))
      (node (ref "U3") (pin "17") (pinfunction "Y2_17") (pintype "output"))
    )
    (net (code "31") (name "/A14_FPGA") (class "Default")
      (node (ref "U1") (pin "142") (pinfunction "IO79_142") (pintype "bidirectional"))
      (node (ref "U3") (pin "3") (pinfunction "A2_3") (pintype "input"))
    )
    (net (code "32") (name "/A15") (class "Default")
      (node (ref "HEADER") (pin "19") (pinfunction "A15_19") (pintype "input"))
      (node (ref "U3") (pin "18") (pinfunction "Y1_18") (pintype "output"))
    )
    (net (code "33") (name "/A15_FPGA") (class "Default")
      (node (ref "U1") (pin "143") (pinfunction "IO80_143") (pintype "bidirectional"))
      (node (ref "U3") (pin "2") (pinfunction "A1_2") (pintype "input"))
    )
    (net (code "34") (name "/ASDO") (class "Default")
      (node (ref "U1") (pin "1") (pinfunction "IO1(ASDO)_1") (pintype "bidirectional"))
      (node (ref "U10") (pin "2") (pinfunction "DATA_2") (pintype "output"))
    )
    (net (code "35") (name "/CLK0") (class "Default")
      (node (ref "U1") (pin "17") (pinfunction "CLK0_17") (pintype "input"))
      (node (ref "XO2") (pin "3") (pinfunction "OUT_3") (pintype "output"))
    )
    (net (code "36") (name "/CLK1") (class "Default")
      (node (ref "R39") (pin "2") (pinfunction "2_2") (pintype "passive"))
      (node (ref "U1") (pin "18") (pinfunction "CLK1_18") (pintype "input"))
    )
    (net (code "37") (name "/CLK2") (class "Default")
      (node (ref "R40") (pin "2") (pinfunction "2_2") (pintype "passive"))
      (node (ref "U1") (pin "21") (pinfunction "CLK2_21") (pintype "input"))
    )
    (net (code "38") (name "/CONF_DONE") (class "Default")
      (node (ref "R4") (pin "2") (pinfunction "2_2") (pintype "passive"))
      (node (ref "U1") (pin "83") (pinfunction "CONF_DONE_83") (pintype "bidirectional"))
    )
    (net (code "39") (name "/DATA0") (class "Default")
      (node (ref "U1") (pin "14") (pinfunction "DATA0_14") (pintype "bidirectional"))
      (node (ref "U10") (pin "5") (pinfunction "ASDI_5") (pintype "input"))
    )
    (net (code "40") (name "/DB0") (class "Default")
      (node (ref "HEADER") (pin "28") (pinfunction "DB0_28") (pintype "bidirectional"))
      (node (ref "U7") (pin "14") (pinfunction "B7_14") (pintype "bidirectional"))
    )
    (net (code "41") (name "/DB0_FPGA") (class "Default")
      (node (ref "U1") (pin "3") (pinfunction "IO3_3") (pintype "bidirectional"))
      (node (ref "U7") (pin "10") (pinfunction "A7_10") (pintype "bidirectional"))
    )
    (net (code "42") (name "/DB1") (class "Default")
      (node (ref "HEADER") (pin "27") (pinfunction "DB1_27") (pintype "bidirectional"))
      (node (ref "U7") (pin "15") (pinfunction "B6_15") (pintype "bidirectional"))
    )
    (net (code "43") (name "/DB1_FPGA") (class "Default")
      (node (ref "U1") (pin "4") (pinfunction "IO4_4") (pintype "bidirectional"))
      (node (ref "U7") (pin "9") (pinfunction "A6_9") (pintype "bidirectional"))
    )
    (net (code "44") (name "/DB2") (class "Default")
      (node (ref "HEADER") (pin "26") (pinfunction "DB2_26") (pintype "bidirectional"))
      (node (ref "U7") (pin "16") (pinfunction "B5_16") (pintype "bidirectional"))
    )
    (net (code "45") (name "/DB2_FPGA") (class "Default")
      (node (ref "U1") (pin "7") (pinfunction "IO5_7") (pintype "bidirectional"))
      (node (ref "U7") (pin "8") (pinfunction "A5_8") (pintype "bidirectional"))
    )
    (net (code "46") (name "/DB3") (class "Default")
      (node (ref "HEADER") (pin "25") (pinfunction "DB3_25") (pintype "bidirectional"))
      (node (ref "U7") (pin "17") (pinfunction "B4_17") (pintype "bidirectional"))
    )
    (net (code "47") (name "/DB3_FPGA") (class "Default")
      (node (ref "U1") (pin "8") (pinfunction "IO6_8") (pintype "bidirectional"))
      (node (ref "U7") (pin "7") (pinfunction "A4_7") (pintype "bidirectional"))
    )
    (net (code "48") (name "/DB4") (class "Default")
      (node (ref "HEADER") (pin "24") (pinfunction "DB4_24") (pintype "bidirectional"))
      (node (ref "U7") (pin "18") (pinfunction "B3_18") (pintype "bidirectional"))
    )
    (net (code "49") (name "/DB4_FPGA") (class "Default")
      (node (ref "U1") (pin "9") (pinfunction "IO7_9") (pintype "bidirectional"))
      (node (ref "U7") (pin "6") (pinfunction "A3_6") (pintype "bidirectional"))
    )
    (net (code "50") (name "/DB5") (class "Default")
      (node (ref "HEADER") (pin "23") (pinfunction "DB5_23") (pintype "bidirectional"))
      (node (ref "U7") (pin "19") (pinfunction "B2_19") (pintype "bidirectional"))
    )
    (net (code "51") (name "/DB5_FPGA") (class "Default")
      (node (ref "U1") (pin "24") (pinfunction "IO8_24") (pintype "bidirectional"))
      (node (ref "U7") (pin "5") (pinfunction "A2_5") (pintype "bidirectional"))
    )
    (net (code "52") (name "/DB6") (class "Default")
      (node (ref "HEADER") (pin "22") (pinfunction "DB6_22") (pintype "bidirectional"))
      (node (ref "U7") (pin "20") (pinfunction "B1_20") (pintype "bidirectional"))
    )
    (net (code "53") (name "/DB6_FPGA") (class "Default")
      (node (ref "U1") (pin "25") (pinfunction "IO9_25") (pintype "bidirectional"))
      (node (ref "U7") (pin "4") (pinfunction "A1_4") (pintype "bidirectional"))
    )
    (net (code "54") (name "/DB7") (class "Default")
      (node (ref "HEADER") (pin "21") (pinfunction "DB7_21") (pintype "bidirectional"))
      (node (ref "U7") (pin "21") (pinfunction "B0_21") (pintype "bidirectional"))
    )
    (net (code "55") (name "/DB7_FPGA") (class "Default")
      (node (ref "U1") (pin "26") (pinfunction "IO10_26") (pintype "bidirectional"))
      (node (ref "U7") (pin "3") (pinfunction "A0_3") (pintype "bidirectional"))
    )
    (net (code "56") (name "/DB_DIR") (class "Default")
      (node (ref "U1") (pin "144") (pinfunction "IO81_144") (pintype "bidirectional"))
      (node (ref "U7") (pin "2") (pinfunction "DIR_2") (pintype "input"))
    )
    (net (code "57") (name "/DCLK") (class "Default")
      (node (ref "U1") (pin "15") (pinfunction "DCLK_15") (pintype "bidirectional"))
      (node (ref "U10") (pin "6") (pinfunction "DCLK_6") (pintype "input"))
    )
    (net (code "58") (name "/DENDY") (class "Default")
      (node (ref "JP8") (pin "1") (pinfunction "1_1") (pintype "passive"))
      (node (ref "U1") (pin "30") (pinfunction "IO13_30") (pintype "bidirectional"))
    )
    (net (code "59") (name "/DMC") (class "Default")
      (node (ref "R10") (pin "1") (pinfunction "1_1") (pintype "passive"))
      (node (ref "U1") (pin "75") (pinfunction "IO42_75") (pintype "bidirectional"))
    )
    (net (code "60") (name "/DMC0") (class "Default")
      (node (ref "RN3") (pin "2") (pinfunction "1_2") (pintype "passive"))
      (node (ref "U1") (pin "40") (pinfunction "IO16_40") (pintype "bidirectional"))
    )
    (net (code "61") (name "/DMC1") (class "Default")
      (node (ref "RN3") (pin "3") (pinfunction "1_3") (pintype "passive"))
      (node (ref "U1") (pin "41") (pinfunction "IO17_41") (pintype "bidirectional"))
    )
    (net (code "62") (name "/DMC2") (class "Default")
      (node (ref "RN3") (pin "4") (pinfunction "1_4") (pintype "passive"))
      (node (ref "U1") (pin "42") (pinfunction "IO18_42") (pintype "bidirectional"))
    )
    (net (code "63") (name "/DMC3") (class "Default")
      (node (ref "RN4") (pin "1") (pinfunction "1_1") (pintype "passive"))
      (node (ref "U1") (pin "43") (pinfunction "IO19_43") (pintype "bidirectional"))
    )
    (net (code "64") (name "/DMC4") (class "Default")
      (node (ref "RN4") (pin "2") (pinfunction "1_2") (pintype "passive"))
      (node (ref "U1") (pin "44") (pinfunction "IO20_44") (pintype "bidirectional"))
    )
    (net (code "65") (name "/DMC5") (class "Default")
      (node (ref "RN4") (pin "3") (pinfunction "1_3") (pintype "passive"))
      (node (ref "U1") (pin "45") (pinfunction "IO21_45") (pintype "bidirectional"))
    )
    (net (code "66") (name "/DMC6") (class "Default")
      (node (ref "RN4") (pin "4") (pinfunction "1_4") (pintype "passive"))
      (node (ref "U1") (pin "47") (pinfunction "IO22_47") (pintype "bidirectional"))
    )
    (net (code "67") (name "/EXT_CLK") (class "Default")
      (node (ref "HEADER") (pin "29") (pinfunction "CLK_29") (pintype "output"))
      (node (ref "R38") (pin "1") (pinfunction "1_1") (pintype "passive"))
      (node (ref "U9") (pin "2") (pinfunction "A_2") (pintype "input"))
    )
    (net (code "68") (name "/IRQ_FPGA") (class "Default")
      (node (ref "U1") (pin "103") (pinfunction "IO57_103") (pintype "bidirectional"))
      (node (ref "U8") (pin "4") (pinfunction "OUT_4") (pintype "output"))
    )
    (net (code "69") (name "/J1") (class "Default")
      (node (ref "JP9") (pin "1") (pinfunction "1_1") (pintype "passive"))
      (node (ref "U1") (pin "28") (pinfunction "IO12_28") (pintype "bidirectional"))
    )
    (net (code "70") (name "/J2") (class "Default")
      (node (ref "JP4") (pin "1") (pinfunction "1_1") (pintype "passive"))
      (node (ref "U1") (pin "27") (pinfunction "IO11_27") (pintype "bidirectional"))
    )
    (net (code "71") (name "/M2") (class "Default")
      (node (ref "HEADER") (pin "31") (pinfunction "M2_31") (pintype "input"))
      (node (ref "U5") (pin "11") (pinfunction "Y8_11") (pintype "output"))
    )
    (net (code "72") (name "/M2_FPGA") (class "Default")
      (node (ref "U1") (pin "129") (pinfunction "IO70_129") (pintype "bidirectional"))
      (node (ref "U5") (pin "9") (pinfunction "A8_9") (pintype "input"))
    )
    (net (code "73") (name "/NCE") (class "Default")
      (node (ref "R7") (pin "1") (pinfunction "1_1") (pintype "passive"))
      (node (ref "U1") (pin "16") (pinfunction "NCE_16") (pintype "input"))
    )
    (net (code "74") (name "/NCONFIG") (class "Default")
      (node (ref "R6") (pin "1") (pinfunction "1_1") (pintype "passive"))
      (node (ref "U1") (pin "20") (pinfunction "NCONFIG_20") (pintype "input"))
    )
    (net (code "75") (name "/NMI_FPGA") (class "Default")
      (node (ref "U1") (pin "101") (pinfunction "IO56_101") (pintype "bidirectional"))
      (node (ref "U6") (pin "4") (pinfunction "OUT_4") (pintype "output"))
    )
    (net (code "76") (name "/NSTATUS") (class "Default")
      (node (ref "R5") (pin "1") (pinfunction "1_1") (pintype "passive"))
      (node (ref "U1") (pin "82") (pinfunction "NSTATUS_82") (pintype "bidirectional"))
    )
    (net (code "77") (name "/NTSC{slash}PAL") (class "Default")
      (node (ref "JP2") (pin "1") (pinfunction "1_1") (pintype "passive"))
      (node (ref "U1") (pin "31") (pinfunction "IO14_31") (pintype "bidirectional"))
    )
    (net (code "78") (name "/OUT0") (class "Default")
      (node (ref "HEADER") (pin "39") (pinfunction "OUT0_39") (pintype "input"))
      (node (ref "U5") (pin "17") (pinfunction "Y2_17") (pintype "output"))
    )
    (net (code "79") (name "/OUT0_FPGA") (class "Default")
      (node (ref "U1") (pin "121") (pinfunction "IO66_121") (pintype "bidirectional"))
      (node (ref "U5") (pin "3") (pinfunction "A2_3") (pintype "input"))
    )
    (net (code "80") (name "/OUT1") (class "Default")
      (node (ref "HEADER") (pin "38") (pinfunction "OUT1_38") (pintype "input"))
      (node (ref "U5") (pin "16") (pinfunction "Y3_16") (pintype "output"))
    )
    (net (code "81") (name "/OUT1_FPGA") (class "Default")
      (node (ref "U1") (pin "122") (pinfunction "IO67_122") (pintype "bidirectional"))
      (node (ref "U5") (pin "4") (pinfunction "A3_4") (pintype "input"))
    )
    (net (code "82") (name "/OUT2") (class "Default")
      (node (ref "HEADER") (pin "37") (pinfunction "OUT2_37") (pintype "input"))
      (node (ref "U5") (pin "15") (pinfunction "Y4_15") (pintype "output"))
    )
    (net (code "83") (name "/OUT2_FPGA") (class "Default")
      (node (ref "U1") (pin "125") (pinfunction "IO68_125") (pintype "bidirectional"))
      (node (ref "U5") (pin "5") (pinfunction "A4_5") (pintype "input"))
    )
    (net (code "84") (name "/RES_FPGA") (class "Default")
      (node (ref "U1") (pin "99") (pinfunction "IO54_99") (pintype "bidirectional"))
      (node (ref "U2") (pin "4") (pinfunction "OUT_4") (pintype "output"))
    )
    (net (code "85") (name "/RND") (class "Default")
      (node (ref "R12") (pin "1") (pinfunction "1_1") (pintype "passive"))
      (node (ref "U1") (pin "76") (pinfunction "IO43_76") (pintype "bidirectional"))
    )
    (net (code "86") (name "/R{slash}W") (class "Default")
      (node (ref "HEADER") (pin "34") (pinfunction "R/W_34") (pintype "input"))
      (node (ref "U5") (pin "12") (pinfunction "Y7_12") (pintype "output"))
    )
    (net (code "87") (name "/R{slash}W_FPGA") (class "Default")
      (node (ref "U1") (pin "126") (pinfunction "IO69_126") (pintype "bidirectional"))
      (node (ref "U5") (pin "8") (pinfunction "A7_8") (pintype "input"))
    )
    (net (code "88") (name "/SND0") (class "Default")
      (node (ref "R25") (pin "1") (pinfunction "1_1") (pintype "passive"))
      (node (ref "U1") (pin "57") (pinfunction "IO28_57") (pintype "bidirectional"))
    )
    (net (code "89") (name "/SND1") (class "Default")
      (node (ref "R26") (pin "1") (pinfunction "1_1") (pintype "passive"))
      (node (ref "U1") (pin "55") (pinfunction "IO27_55") (pintype "bidirectional"))
    )
    (net (code "90") (name "/SND2") (class "Default")
      (node (ref "RN1") (pin "1") (pinfunction "1_1") (pintype "passive"))
      (node (ref "U1") (pin "53") (pinfunction "IO26_53") (pintype "bidirectional"))
    )
    (net (code "91") (name "/SND3") (class "Default")
      (node (ref "RN1") (pin "2") (pinfunction "1_2") (pintype "passive"))
      (node (ref "U1") (pin "52") (pinfunction "IO25_52") (pintype "bidirectional"))
    )
    (net (code "92") (name "/SND4") (class "Default")
      (node (ref "RN1") (pin "3") (pinfunction "1_3") (pintype "passive"))
      (node (ref "U1") (pin "51") (pinfunction "IO24_51") (pintype "bidirectional"))
    )
    (net (code "93") (name "/SND5") (class "Default")
      (node (ref "RN1") (pin "4") (pinfunction "1_4") (pintype "passive"))
      (node (ref "U1") (pin "48") (pinfunction "IO23_48") (pintype "bidirectional"))
    )
    (net (code "94") (name "/SND_L") (class "Default")
      (node (ref "C41") (pin "1") (pinfunction "1_1") (pintype "passive"))
      (node (ref "JP1") (pin "1") (pinfunction "1_1") (pintype "passive"))
      (node (ref "JP6") (pin "2") (pinfunction "2_2") (pintype "passive"))
    )
    (net (code "95") (name "/SND_R") (class "Default")
      (node (ref "C42") (pin "1") (pinfunction "1_1") (pintype "passive"))
      (node (ref "JP5") (pin "1") (pinfunction "1_1") (pintype "passive"))
      (node (ref "JP7") (pin "2") (pinfunction "2_2") (pintype "passive"))
    )
    (net (code "96") (name "/SQA") (class "Default")
      (node (ref "R18") (pin "1") (pinfunction "1_1") (pintype "passive"))
      (node (ref "U1") (pin "86") (pinfunction "IO47_86") (pintype "bidirectional"))
    )
    (net (code "97") (name "/SQB") (class "Default")
      (node (ref "R16") (pin "1") (pinfunction "1_1") (pintype "passive"))
      (node (ref "U1") (pin "81") (pinfunction "IO46_81") (pintype "bidirectional"))
    )
    (net (code "98") (name "/TCK") (class "Default")
      (node (ref "R8") (pin "1") (pinfunction "1_1") (pintype "passive"))
      (node (ref "U1") (pin "12") (pinfunction "TCK_12") (pintype "input"))
      (node (ref "X1") (pin "1") (pinfunction "S_1") (pintype "passive"))
    )
    (net (code "99") (name "/TDI") (class "Default")
      (node (ref "R2") (pin "1") (pinfunction "1_1") (pintype "passive"))
      (node (ref "U1") (pin "13") (pinfunction "TDI_13") (pintype "input"))
      (node (ref "X1") (pin "9") (pinfunction "S_9") (pintype "passive"))
    )
    (net (code "100") (name "/TDO") (class "Default")
      (node (ref "U1") (pin "10") (pinfunction "TDO_10") (pintype "output"))
      (node (ref "X1") (pin "3") (pinfunction "S_3") (pintype "passive"))
    )
    (net (code "101") (name "/TMS") (class "Default")
      (node (ref "R3") (pin "1") (pinfunction "1_1") (pintype "passive"))
      (node (ref "U1") (pin "11") (pinfunction "TMS_11") (pintype "input"))
      (node (ref "X1") (pin "5") (pinfunction "S_5") (pintype "passive"))
    )
    (net (code "102") (name "/TRIA") (class "Default")
      (node (ref "R14") (pin "1") (pinfunction "1_1") (pintype "passive"))
      (node (ref "U1") (pin "80") (pinfunction "IO45_80") (pintype "bidirectional"))
    )
    (net (code "103") (name "/VPPL1") (class "Default")
      (node (ref "C12") (pin "1") (pinfunction "1_1") (pintype "passive"))
      (node (ref "C13") (pin "1") (pinfunction "1_1") (pintype "passive"))
      (node (ref "L2") (pin "2") (pinfunction "2_2") (pintype "passive"))
      (node (ref "U1") (pin "35") (pinfunction "VPLL1_35") (pintype "power_in"))
      (node (ref "U1") (pin "37") (pinfunction "VAPLL1_37") (pintype "power_in"))
    )
    (net (code "104") (name "/VPPL2") (class "Default")
      (node (ref "C10") (pin "1") (pinfunction "1_1") (pintype "passive"))
      (node (ref "C11") (pin "1") (pinfunction "1_1") (pintype "passive"))
      (node (ref "L1") (pin "1") (pinfunction "1_1") (pintype "passive"))
      (node (ref "U1") (pin "107") (pinfunction "VPLL2_107") (pintype "power_in"))
      (node (ref "U1") (pin "109") (pinfunction "VAPLL2_109") (pintype "power_in"))
    )
    (net (code "105") (name "/{slash}CSO") (class "Default")
      (node (ref "U1") (pin "2") (pinfunction "IO2(/CSO)_2") (pintype "bidirectional"))
      (node (ref "U10") (pin "1") (pinfunction "/CS_1") (pintype "input"))
    )
    (net (code "106") (name "/{slash}IN0") (class "Default")
      (node (ref "HEADER") (pin "36") (pinfunction "/IN0_36") (pintype "input"))
      (node (ref "U5") (pin "14") (pinfunction "Y5_14") (pintype "output"))
    )
    (net (code "107") (name "/{slash}IN0_FPGA") (class "Default")
      (node (ref "U1") (pin "133") (pinfunction "IO72_133") (pintype "bidirectional"))
      (node (ref "U5") (pin "6") (pinfunction "A5_6") (pintype "input"))
    )
    (net (code "108") (name "/{slash}IN1") (class "Default")
      (node (ref "HEADER") (pin "35") (pinfunction "/IN1_35") (pintype "input"))
      (node (ref "U5") (pin "13") (pinfunction "Y6_13") (pintype "output"))
    )
    (net (code "109") (name "/{slash}IN1_FPGA") (class "Default")
      (node (ref "U1") (pin "132") (pinfunction "IO71_132") (pintype "bidirectional"))
      (node (ref "U5") (pin "7") (pinfunction "A6_7") (pintype "input"))
    )
    (net (code "110") (name "/{slash}IRQ") (class "Default")
      (node (ref "HEADER") (pin "32") (pinfunction "/IRQ_32") (pintype "output"))
      (node (ref "U8") (pin "2") (pinfunction "IN_2") (pintype "input"))
    )
    (net (code "111") (name "/{slash}NMI") (class "Default")
      (node (ref "HEADER") (pin "33") (pinfunction "/NMI_33") (pintype "output"))
      (node (ref "U6") (pin "2") (pinfunction "IN_2") (pintype "input"))
    )
    (net (code "112") (name "/{slash}OE") (class "Default")
      (node (ref "U1") (pin "100") (pinfunction "IO55_100") (pintype "bidirectional"))
      (node (ref "U3") (pin "1") (pinfunction "/OE1_1") (pintype "input"))
      (node (ref "U4") (pin "1") (pinfunction "/OE1_1") (pintype "input"))
      (node (ref "U5") (pin "19") (pinfunction "/OE2_19") (pintype "input"))
      (node (ref "U7") (pin "22") (pinfunction "/OE_22") (pintype "input"))
    )
    (net (code "113") (name "/{slash}RES") (class "Default")
      (node (ref "HEADER") (pin "3") (pinfunction "/RES_3") (pintype "output"))
      (node (ref "R1") (pin "2") (pinfunction "2_2") (pintype "passive"))
      (node (ref "U2") (pin "2") (pinfunction "IN_2") (pintype "input"))
    )
    (net (code "114") (name "GND") (class "Default")
      (node (ref "C1") (pin "2") (pinfunction "2_2") (pintype "passive"))
      (node (ref "C10") (pin "2") (pinfunction "2_2") (pintype "passive"))
      (node (ref "C11") (pin "2") (pinfunction "2_2") (pintype "passive"))
      (node (ref "C12") (pin "2") (pinfunction "2_2") (pintype "passive"))
      (node (ref "C13") (pin "2") (pinfunction "2_2") (pintype "passive"))
      (node (ref "C14") (pin "1") (pinfunction "1_1") (pintype "passive"))
      (node (ref "C15") (pin "1") (pinfunction "1_1") (pintype "passive"))
      (node (ref "C16") (pin "1") (pinfunction "1_1") (pintype "passive"))
      (node (ref "C17") (pin "1") (pinfunction "1_1") (pintype "passive"))
      (node (ref "C18") (pin "1") (pinfunction "1_1") (pintype "passive"))
      (node (ref "C19") (pin "1") (pinfunction "1_1") (pintype "passive"))
      (node (ref "C2") (pin "2") (pinfunction "2_2") (pintype "passive"))
      (node (ref "C20") (pin "1") (pinfunction "1_1") (pintype "passive"))
      (node (ref "C21") (pin "1") (pinfunction "1_1") (pintype "passive"))
      (node (ref "C22") (pin "1") (pinfunction "1_1") (pintype "passive"))
      (node (ref "C23") (pin "1") (pinfunction "1_1") (pintype "passive"))
      (node (ref "C24") (pin "2") (pinfunction "2_2") (pintype "passive"))
      (node (ref "C25") (pin "2") (pinfunction "2_2") (pintype "passive"))
      (node (ref "C26") (pin "2") (pinfunction "2_2") (pintype "passive"))
      (node (ref "C27") (pin "2") (pinfunction "2_2") (pintype "passive"))
      (node (ref "C28") (pin "2") (pinfunction "2_2") (pintype "passive"))
      (node (ref "C29") (pin "2") (pinfunction "2_2") (pintype "passive"))
      (node (ref "C3") (pin "2") (pinfunction "2_2") (pintype "passive"))
      (node (ref "C30") (pin "2") (pinfunction "2_2") (pintype "passive"))
      (node (ref "C31") (pin "2") (pinfunction "2_2") (pintype "passive"))
      (node (ref "C32") (pin "2") (pinfunction "2_2") (pintype "passive"))
      (node (ref "C33") (pin "2") (pinfunction "2_2") (pintype "passive"))
      (node (ref "C34") (pin "2") (pinfunction "2_2") (pintype "passive"))
      (node (ref "C35") (pin "2") (pinfunction "2_2") (pintype "passive"))
      (node (ref "C36") (pin "2") (pinfunction "2_2") (pintype "passive"))
      (node (ref "C37") (pin "2") (pinfunction "2_2") (pintype "passive"))
      (node (ref "C39") (pin "1") (pinfunction "1_1") (pintype "passive"))
      (node (ref "C4") (pin "-") (pinfunction "-_-") (pintype "passive"))
      (node (ref "C40") (pin "2") (pinfunction "2_2") (pintype "passive"))
      (node (ref "C43") (pin "1") (pinfunction "1_1") (pintype "passive"))
      (node (ref "C44") (pin "2") (pinfunction "2_2") (pintype "passive"))
      (node (ref "C47") (pin "2") (pinfunction "2_2") (pintype "passive"))
      (node (ref "C48") (pin "2") (pinfunction "2_2") (pintype "passive"))
      (node (ref "C5") (pin "2") (pinfunction "2_2") (pintype "passive"))
      (node (ref "C6") (pin "2") (pinfunction "2_2") (pintype "passive"))
      (node (ref "C7") (pin "2") (pinfunction "2_2") (pintype "passive"))
      (node (ref "C8") (pin "2") (pinfunction "2_2") (pintype "passive"))
      (node (ref "C9") (pin "-") (pinfunction "-_-") (pintype "passive"))
      (node (ref "HEADER") (pin "20") (pinfunction "GND_20") (pintype "power_in"))
      (node (ref "HEADER") (pin "30") (pinfunction "DBG_30") (pintype "input"))
      (node (ref "JP2") (pin "2") (pinfunction "2_2") (pintype "passive"))
      (node (ref "JP4") (pin "2") (pinfunction "2_2") (pintype "passive"))
      (node (ref "JP8") (pin "2") (pinfunction "2_2") (pintype "passive"))
      (node (ref "JP9") (pin "2") (pinfunction "2_2") (pintype "passive"))
      (node (ref "LED1") (pin "C@1") (pinfunction "C_C@1") (pintype "passive"))
      (node (ref "R24") (pin "1") (pinfunction "1_1") (pintype "passive"))
      (node (ref "R28") (pin "1") (pinfunction "1_1") (pintype "passive"))
      (node (ref "R35") (pin "2") (pinfunction "2_2") (pintype "passive"))
      (node (ref "R37") (pin "1") (pinfunction "1_1") (pintype "passive"))
      (node (ref "R42") (pin "2") (pinfunction "2_2") (pintype "passive"))
      (node (ref "R47") (pin "2") (pinfunction "2_2") (pintype "passive"))
      (node (ref "R52") (pin "2") (pinfunction "2_2") (pintype "passive"))
      (node (ref "R7") (pin "2") (pinfunction "2_2") (pintype "passive"))
      (node (ref "R8") (pin "2") (pinfunction "2_2") (pintype "passive"))
      (node (ref "RN3") (pin "1") (pinfunction "1_1") (pintype "passive"))
      (node (ref "U1") (pin "105") (pinfunction "GND_105") (pintype "power_in"))
      (node (ref "U1") (pin "106") (pinfunction "GPLL2_106") (pintype "power_in"))
      (node (ref "U1") (pin "108") (pinfunction "GPLL2_108") (pintype "power_in"))
      (node (ref "U1") (pin "110") (pinfunction "GAPLL2_110") (pintype "power_in"))
      (node (ref "U1") (pin "111") (pinfunction "GND_111") (pintype "power_in"))
      (node (ref "U1") (pin "117") (pinfunction "GND_117") (pintype "power_in"))
      (node (ref "U1") (pin "123") (pinfunction "GND_123") (pintype "power_in"))
      (node (ref "U1") (pin "128") (pinfunction "GND_128") (pintype "power_in"))
      (node (ref "U1") (pin "130") (pinfunction "GND_130") (pintype "power_in"))
      (node (ref "U1") (pin "140") (pinfunction "GND_140") (pintype "power_in"))
      (node (ref "U1") (pin "19") (pinfunction "GND_19") (pintype "power_in"))
      (node (ref "U1") (pin "33") (pinfunction "GND_33") (pintype "power_in"))
      (node (ref "U1") (pin "34") (pinfunction "GPLL1_34") (pintype "power_in"))
      (node (ref "U1") (pin "36") (pinfunction "GPLL1_36") (pintype "power_in"))
      (node (ref "U1") (pin "38") (pinfunction "GAPLL1_38") (pintype "power_in"))
      (node (ref "U1") (pin "39") (pinfunction "GND_39") (pintype "power_in"))
      (node (ref "U1") (pin "49") (pinfunction "GND_49") (pintype "power_in"))
      (node (ref "U1") (pin "56") (pinfunction "GND_56") (pintype "power_in"))
      (node (ref "U1") (pin "6") (pinfunction "GND_6") (pintype "power_in"))
      (node (ref "U1") (pin "61") (pinfunction "GND_61") (pintype "power_in"))
      (node (ref "U1") (pin "68") (pinfunction "GND_68") (pintype "power_in"))
      (node (ref "U1") (pin "78") (pinfunction "GND_78") (pintype "power_in"))
      (node (ref "U1") (pin "84") (pinfunction "MSEL1_84") (pintype "input"))
      (node (ref "U1") (pin "85") (pinfunction "MSEL0_85") (pintype "input"))
      (node (ref "U1") (pin "98") (pinfunction "GND_98") (pintype "power_in"))
      (node (ref "U10") (pin "4") (pinfunction "GND_4") (pintype "power_in"))
      (node (ref "U11") (pin "4") (pinfunction "V-_4") (pintype "power_in"))
      (node (ref "U2") (pin "3") (pinfunction "GND_3") (pintype "power_in"))
      (node (ref "U3") (pin "10") (pinfunction "GND_10") (pintype "power_in"))
      (node (ref "U3") (pin "19") (pinfunction "/OE2_19") (pintype "input"))
      (node (ref "U4") (pin "10") (pinfunction "GND_10") (pintype "power_in"))
      (node (ref "U4") (pin "19") (pinfunction "/OE2_19") (pintype "input"))
      (node (ref "U5") (pin "1") (pinfunction "/OE1_1") (pintype "input"))
      (node (ref "U5") (pin "10") (pinfunction "GND_10") (pintype "power_in"))
      (node (ref "U5") (pin "2") (pinfunction "A1_2") (pintype "input"))
      (node (ref "U6") (pin "3") (pinfunction "GND_3") (pintype "power_in"))
      (node (ref "U7") (pin "11") (pinfunction "GND_11") (pintype "power_in"))
      (node (ref "U7") (pin "12") (pinfunction "GND_12") (pintype "power_in"))
      (node (ref "U7") (pin "13") (pinfunction "GND_13") (pintype "power_in"))
      (node (ref "U8") (pin "3") (pinfunction "GND_3") (pintype "power_in"))
      (node (ref "U9") (pin "3") (pinfunction "GND_3") (pintype "power_in"))
      (node (ref "VR1") (pin "1") (pinfunction "GND_1") (pintype "power_in"))
      (node (ref "VR2") (pin "1") (pinfunction "GND_1") (pintype "bidirectional"))
      (node (ref "X1") (pin "10") (pinfunction "S_10") (pintype "passive"))
      (node (ref "X1") (pin "2") (pinfunction "S_2") (pintype "passive"))
      (node (ref "X2") (pin "1") (pinfunction "1_1") (pintype "passive"))
      (node (ref "XO1") (pin "2") (pinfunction "GND_2") (pintype "power_in"))
      (node (ref "XO2") (pin "2") (pinfunction "GND_2") (pintype "power_in"))
    )
    (net (code "115") (name "Net-(C31-Pad1)") (class "Default")
      (node (ref "C31") (pin "1") (pinfunction "1_1") (pintype "passive"))
      (node (ref "R10") (pin "2") (pinfunction "2_2") (pintype "passive"))
      (node (ref "R11") (pin "1") (pinfunction "1_1") (pintype "passive"))
    )
    (net (code "116") (name "Net-(C32-Pad1)") (class "Default")
      (node (ref "C32") (pin "1") (pinfunction "1_1") (pintype "passive"))
      (node (ref "R12") (pin "2") (pinfunction "2_2") (pintype "passive"))
      (node (ref "R13") (pin "1") (pinfunction "1_1") (pintype "passive"))
    )
    (net (code "117") (name "Net-(C33-Pad1)") (class "Default")
      (node (ref "C33") (pin "1") (pinfunction "1_1") (pintype "passive"))
      (node (ref "R14") (pin "2") (pinfunction "2_2") (pintype "passive"))
      (node (ref "R15") (pin "1") (pinfunction "1_1") (pintype "passive"))
    )
    (net (code "118") (name "Net-(C34-Pad1)") (class "Default")
      (node (ref "C34") (pin "1") (pinfunction "1_1") (pintype "passive"))
      (node (ref "R16") (pin "2") (pinfunction "2_2") (pintype "passive"))
      (node (ref "R17") (pin "1") (pinfunction "1_1") (pintype "passive"))
    )
    (net (code "119") (name "Net-(C35-Pad1)") (class "Default")
      (node (ref "C35") (pin "1") (pinfunction "1_1") (pintype "passive"))
      (node (ref "R18") (pin "2") (pinfunction "2_2") (pintype "passive"))
      (node (ref "R19") (pin "1") (pinfunction "1_1") (pintype "passive"))
    )
    (net (code "120") (name "Net-(C38-Pad2)") (class "Default")
      (node (ref "C38") (pin "2") (pinfunction "2_2") (pintype "passive"))
      (node (ref "JP3") (pin "1") (pinfunction "1_1") (pintype "passive"))
    )
    (net (code "121") (name "Net-(C39-Pad2)") (class "Default")
      (node (ref "C39") (pin "2") (pinfunction "2_2") (pintype "passive"))
      (node (ref "R36") (pin "1") (pinfunction "1_1") (pintype "passive"))
      (node (ref "R37") (pin "2") (pinfunction "2_2") (pintype "passive"))
      (node (ref "R38") (pin "2") (pinfunction "2_2") (pintype "passive"))
    )
    (net (code "122") (name "Net-(C45-Pad+)") (class "Default")
      (node (ref "C45") (pin "+") (pinfunction "+_+") (pintype "passive"))
      (node (ref "R43") (pin "2") (pinfunction "2_2") (pintype "passive"))
    )
    (net (code "123") (name "Net-(C46-Pad+)") (class "Default")
      (node (ref "C46") (pin "+") (pinfunction "+_+") (pintype "passive"))
      (node (ref "R48") (pin "2") (pinfunction "2_2") (pintype "passive"))
    )
    (net (code "124") (name "Net-(C47-Pad1)") (class "Default")
      (node (ref "C47") (pin "1") (pinfunction "1_1") (pintype "passive"))
      (node (ref "C48") (pin "1") (pinfunction "1_1") (pintype "passive"))
      (node (ref "R44") (pin "1") (pinfunction "1_1") (pintype "passive"))
      (node (ref "R49") (pin "1") (pinfunction "1_1") (pintype "passive"))
      (node (ref "R51") (pin "2") (pinfunction "2_2") (pintype "passive"))
      (node (ref "R52") (pin "1") (pinfunction "1_1") (pintype "passive"))
    )
    (net (code "125") (name "Net-(JP1-Pad2)") (class "Default")
      (node (ref "JP1") (pin "2") (pinfunction "2_2") (pintype "passive"))
      (node (ref "R29") (pin "2") (pinfunction "2_2") (pintype "passive"))
      (node (ref "R33") (pin "1") (pinfunction "1_1") (pintype "passive"))
    )
    (net (code "126") (name "Net-(JP5-Pad2)") (class "Default")
      (node (ref "JP5") (pin "2") (pinfunction "2_2") (pintype "passive"))
      (node (ref "R30") (pin "2") (pinfunction "2_2") (pintype "passive"))
      (node (ref "R34") (pin "1") (pinfunction "1_1") (pintype "passive"))
    )
    (net (code "127") (name "Net-(JP6-Pad1)") (class "Default")
      (node (ref "JP6") (pin "1") (pinfunction "1_1") (pintype "passive"))
      (node (ref "R20") (pin "2") (pinfunction "2_2") (pintype "passive"))
      (node (ref "R22") (pin "1") (pinfunction "1_1") (pintype "passive"))
    )
    (net (code "128") (name "Net-(JP7-Pad1)") (class "Default")
      (node (ref "JP7") (pin "1") (pinfunction "1_1") (pintype "passive"))
      (node (ref "R21") (pin "2") (pinfunction "2_2") (pintype "passive"))
      (node (ref "R23") (pin "1") (pinfunction "1_1") (pintype "passive"))
    )
    (net (code "129") (name "Net-(LED1-A)") (class "Default")
      (node (ref "LED1") (pin "A@1") (pinfunction "A_A@1") (pintype "passive"))
      (node (ref "R9") (pin "1") (pinfunction "1_1") (pintype "passive"))
    )
    (net (code "130") (name "Net-(R11-Pad2)") (class "Default")
      (node (ref "R11") (pin "2") (pinfunction "2_2") (pintype "passive"))
      (node (ref "R13") (pin "2") (pinfunction "2_2") (pintype "passive"))
      (node (ref "R15") (pin "2") (pinfunction "2_2") (pintype "passive"))
      (node (ref "R20") (pin "1") (pinfunction "1_1") (pintype "passive"))
      (node (ref "R21") (pin "1") (pinfunction "1_1") (pintype "passive"))
    )
    (net (code "131") (name "Net-(R17-Pad2)") (class "Default")
      (node (ref "R17") (pin "2") (pinfunction "2_2") (pintype "passive"))
      (node (ref "R19") (pin "2") (pinfunction "2_2") (pintype "passive"))
      (node (ref "R22") (pin "2") (pinfunction "2_2") (pintype "passive"))
      (node (ref "R23") (pin "2") (pinfunction "2_2") (pintype "passive"))
    )
    (net (code "132") (name "Net-(R24-Pad2)") (class "Default")
      (node (ref "R24") (pin "2") (pinfunction "2_2") (pintype "passive"))
      (node (ref "R25") (pin "2") (pinfunction "2_2") (pintype "passive"))
      (node (ref "R27") (pin "2") (pinfunction "2_2") (pintype "passive"))
    )
    (net (code "133") (name "Net-(R33-Pad2)") (class "Default")
      (node (ref "R33") (pin "2") (pinfunction "2_2") (pintype "passive"))
      (node (ref "R34") (pin "2") (pinfunction "2_2") (pintype "passive"))
      (node (ref "R35") (pin "1") (pinfunction "1_1") (pintype "passive"))
    )
    (net (code "134") (name "Net-(RN1A-2)") (class "Default")
      (node (ref "RN1") (pin "8") (pinfunction "2_8") (pintype "passive"))
      (node (ref "RN2") (pin "1") (pinfunction "1_1") (pintype "passive"))
      (node (ref "RN2") (pin "7") (pinfunction "2_7") (pintype "passive"))
    )
    (net (code "135") (name "Net-(RN1B-2)") (class "Default")
      (node (ref "RN1") (pin "7") (pinfunction "2_7") (pintype "passive"))
      (node (ref "RN2") (pin "2") (pinfunction "1_2") (pintype "passive"))
      (node (ref "RN2") (pin "6") (pinfunction "2_6") (pintype "passive"))
    )
    (net (code "136") (name "Net-(RN1C-2)") (class "Default")
      (node (ref "RN1") (pin "6") (pinfunction "2_6") (pintype "passive"))
      (node (ref "RN2") (pin "3") (pinfunction "1_3") (pintype "passive"))
      (node (ref "RN2") (pin "5") (pinfunction "2_5") (pintype "passive"))
    )
    (net (code "137") (name "Net-(RN1D-2)") (class "Default")
      (node (ref "R28") (pin "2") (pinfunction "2_2") (pintype "passive"))
      (node (ref "R29") (pin "1") (pinfunction "1_1") (pintype "passive"))
      (node (ref "R30") (pin "1") (pinfunction "1_1") (pintype "passive"))
      (node (ref "RN1") (pin "5") (pinfunction "2_5") (pintype "passive"))
      (node (ref "RN2") (pin "4") (pinfunction "1_4") (pintype "passive"))
    )
    (net (code "138") (name "Net-(RN2A-2)") (class "Default")
      (node (ref "R26") (pin "2") (pinfunction "2_2") (pintype "passive"))
      (node (ref "R27") (pin "1") (pinfunction "1_1") (pintype "passive"))
      (node (ref "RN2") (pin "8") (pinfunction "2_8") (pintype "passive"))
    )
    (net (code "139") (name "Net-(RN3A-2)") (class "Default")
      (node (ref "R31") (pin "2") (pinfunction "2_2") (pintype "passive"))
      (node (ref "RN3") (pin "7") (pinfunction "2_7") (pintype "passive"))
      (node (ref "RN3") (pin "8") (pinfunction "2_8") (pintype "passive"))
    )
    (net (code "140") (name "Net-(RN3C-2)") (class "Default")
      (node (ref "R31") (pin "1") (pinfunction "1_1") (pintype "passive"))
      (node (ref "R32") (pin "2") (pinfunction "2_2") (pintype "passive"))
      (node (ref "RN3") (pin "6") (pinfunction "2_6") (pintype "passive"))
    )
    (net (code "141") (name "Net-(RN3D-2)") (class "Default")
      (node (ref "R32") (pin "1") (pinfunction "1_1") (pintype "passive"))
      (node (ref "RN3") (pin "5") (pinfunction "2_5") (pintype "passive"))
      (node (ref "RN5") (pin "8") (pinfunction "2_8") (pintype "passive"))
    )
    (net (code "142") (name "Net-(RN4A-2)") (class "Default")
      (node (ref "RN4") (pin "8") (pinfunction "2_8") (pintype "passive"))
      (node (ref "RN5") (pin "1") (pinfunction "1_1") (pintype "passive"))
      (node (ref "RN5") (pin "7") (pinfunction "2_7") (pintype "passive"))
    )
    (net (code "143") (name "Net-(RN4B-2)") (class "Default")
      (node (ref "RN4") (pin "7") (pinfunction "2_7") (pintype "passive"))
      (node (ref "RN5") (pin "2") (pinfunction "1_2") (pintype "passive"))
      (node (ref "RN5") (pin "6") (pinfunction "2_6") (pintype "passive"))
    )
    (net (code "144") (name "Net-(RN4C-2)") (class "Default")
      (node (ref "RN4") (pin "6") (pinfunction "2_6") (pintype "passive"))
      (node (ref "RN5") (pin "3") (pinfunction "1_3") (pintype "passive"))
      (node (ref "RN5") (pin "5") (pinfunction "2_5") (pintype "passive"))
    )
    (net (code "145") (name "Net-(RN4D-2)") (class "Default")
      (node (ref "RN4") (pin "5") (pinfunction "2_5") (pintype "passive"))
      (node (ref "RN5") (pin "4") (pinfunction "1_4") (pintype "passive"))
    )
    (net (code "146") (name "Net-(U9-Y)") (class "Default")
      (node (ref "R39") (pin "1") (pinfunction "1_1") (pintype "passive"))
      (node (ref "U9") (pin "4") (pinfunction "Y_4") (pintype "output"))
    )
    (net (code "147") (name "Net-(U11A-+IN)") (class "Default")
      (node (ref "C41") (pin "2") (pinfunction "2_2") (pintype "passive"))
      (node (ref "R41") (pin "2") (pinfunction "2_2") (pintype "passive"))
      (node (ref "R42") (pin "1") (pinfunction "1_1") (pintype "passive"))
      (node (ref "U11") (pin "3") (pinfunction "+IN_3") (pintype "input"))
    )
    (net (code "148") (name "Net-(U11A--IN)") (class "Default")
      (node (ref "R44") (pin "2") (pinfunction "2_2") (pintype "passive"))
      (node (ref "R45") (pin "1") (pinfunction "1_1") (pintype "passive"))
      (node (ref "U11") (pin "2") (pinfunction "-IN_2") (pintype "input"))
    )
    (net (code "149") (name "Net-(U11A-OUT)") (class "Default")
      (node (ref "R43") (pin "1") (pinfunction "1_1") (pintype "passive"))
      (node (ref "R45") (pin "2") (pinfunction "2_2") (pintype "passive"))
      (node (ref "U11") (pin "1") (pinfunction "OUT_1") (pintype "output"))
    )
    (net (code "150") (name "Net-(U11B-+IN)") (class "Default")
      (node (ref "C42") (pin "2") (pinfunction "2_2") (pintype "passive"))
      (node (ref "R46") (pin "2") (pinfunction "2_2") (pintype "passive"))
      (node (ref "R47") (pin "1") (pinfunction "1_1") (pintype "passive"))
      (node (ref "U11") (pin "5") (pinfunction "+IN_5") (pintype "input"))
    )
    (net (code "151") (name "Net-(U11B--IN)") (class "Default")
      (node (ref "R49") (pin "2") (pinfunction "2_2") (pintype "passive"))
      (node (ref "R50") (pin "1") (pinfunction "1_1") (pintype "passive"))
      (node (ref "U11") (pin "6") (pinfunction "-IN_6") (pintype "input"))
    )
    (net (code "152") (name "Net-(U11B-OUT)") (class "Default")
      (node (ref "R48") (pin "1") (pinfunction "1_1") (pintype "passive"))
      (node (ref "R50") (pin "2") (pinfunction "2_2") (pintype "passive"))
      (node (ref "U11") (pin "7") (pinfunction "OUT_7") (pintype "output"))
    )
    (net (code "153") (name "Net-(X2B-1)") (class "Default")
      (node (ref "C45") (pin "-") (pinfunction "-_-") (pintype "passive"))
      (node (ref "X2") (pin "2") (pinfunction "1_2") (pintype "passive"))
    )
    (net (code "154") (name "Net-(X2C-1)") (class "Default")
      (node (ref "C46") (pin "-") (pinfunction "-_-") (pintype "passive"))
      (node (ref "X2") (pin "3") (pinfunction "1_3") (pintype "passive"))
    )
    (net (code "155") (name "Net-(XO1-OUT)") (class "Default")
      (node (ref "C38") (pin "1") (pinfunction "1_1") (pintype "passive"))
      (node (ref "R40") (pin "1") (pinfunction "1_1") (pintype "passive"))
      (node (ref "XO1") (pin "3") (pinfunction "OUT_3") (pintype "output"))
    )
    (net (code "156") (name "Net-(XO1-VDD)") (class "Default")
      (node (ref "C36") (pin "1") (pinfunction "1_1") (pintype "passive"))
      (node (ref "L3") (pin "2") (pinfunction "2_2") (pintype "passive"))
      (node (ref "XO1") (pin "4") (pinfunction "VDD_4") (pintype "power_in"))
    )
    (net (code "157") (name "VCCINT") (class "Default")
      (node (ref "C20") (pin "2") (pinfunction "2_2") (pintype "passive"))
      (node (ref "C22") (pin "2") (pinfunction "2_2") (pintype "passive"))
      (node (ref "C28") (pin "1") (pinfunction "1_1") (pintype "passive"))
      (node (ref "C29") (pin "1") (pinfunction "1_1") (pintype "passive"))
      (node (ref "C8") (pin "1") (pinfunction "1_1") (pintype "passive"))
      (node (ref "C9") (pin "+") (pinfunction "+_+") (pintype "passive"))
      (node (ref "L1") (pin "2") (pinfunction "2_2") (pintype "passive"))
      (node (ref "L2") (pin "1") (pinfunction "1_1") (pintype "passive"))
      (node (ref "U1") (pin "124") (pinfunction "VCCINT_124") (pintype "power_in"))
      (node (ref "U1") (pin "131") (pinfunction "VCCINT_131") (pintype "power_in"))
      (node (ref "U1") (pin "50") (pinfunction "VCCINT_50") (pintype "power_in"))
      (node (ref "U1") (pin "62") (pinfunction "VCCINT_62") (pintype "power_in"))
      (node (ref "VR2") (pin "2") (pinfunction "VOUT_2") (pintype "bidirectional"))
    )
    (net (code "158") (name "VCCIO") (class "Default")
      (node (ref "C14") (pin "2") (pinfunction "2_2") (pintype "passive"))
      (node (ref "C16") (pin "2") (pinfunction "2_2") (pintype "passive"))
      (node (ref "C17") (pin "2") (pinfunction "2_2") (pintype "passive"))
      (node (ref "C18") (pin "2") (pinfunction "2_2") (pintype "passive"))
      (node (ref "C19") (pin "2") (pinfunction "2_2") (pintype "passive"))
      (node (ref "C21") (pin "2") (pinfunction "2_2") (pintype "passive"))
      (node (ref "C23") (pin "2") (pinfunction "2_2") (pintype "passive"))
      (node (ref "C24") (pin "1") (pinfunction "1_1") (pintype "passive"))
      (node (ref "C25") (pin "1") (pinfunction "1_1") (pintype "passive"))
      (node (ref "C26") (pin "1") (pinfunction "1_1") (pintype "passive"))
      (node (ref "C27") (pin "1") (pinfunction "1_1") (pintype "passive"))
      (node (ref "C30") (pin "1") (pinfunction "1_1") (pintype "passive"))
      (node (ref "C37") (pin "1") (pinfunction "1_1") (pintype "passive"))
      (node (ref "C40") (pin "1") (pinfunction "1_1") (pintype "passive"))
      (node (ref "C6") (pin "1") (pinfunction "1_1") (pintype "passive"))
      (node (ref "C7") (pin "1") (pinfunction "1_1") (pintype "passive"))
      (node (ref "L3") (pin "1") (pinfunction "1_1") (pintype "passive"))
      (node (ref "R2") (pin "2") (pinfunction "2_2") (pintype "passive"))
      (node (ref "R3") (pin "2") (pinfunction "2_2") (pintype "passive"))
      (node (ref "R36") (pin "2") (pinfunction "2_2") (pintype "passive"))
      (node (ref "R4") (pin "1") (pinfunction "1_1") (pintype "passive"))
      (node (ref "R5") (pin "2") (pinfunction "2_2") (pintype "passive"))
      (node (ref "R6") (pin "2") (pinfunction "2_2") (pintype "passive"))
      (node (ref "U1") (pin "102") (pinfunction "VCCIO3_102") (pintype "power_in"))
      (node (ref "U1") (pin "116") (pinfunction "VCCIO2_116") (pintype "power_in"))
      (node (ref "U1") (pin "127") (pinfunction "VCCIO2_127") (pintype "power_in"))
      (node (ref "U1") (pin "138") (pinfunction "VCCIO2_138") (pintype "power_in"))
      (node (ref "U1") (pin "23") (pinfunction "VCCIO1_23") (pintype "power_in"))
      (node (ref "U1") (pin "29") (pinfunction "VCCIO1_29") (pintype "power_in"))
      (node (ref "U1") (pin "46") (pinfunction "VCCIO4_46") (pintype "power_in"))
      (node (ref "U1") (pin "5") (pinfunction "VCCIO1_5") (pintype "power_in"))
      (node (ref "U1") (pin "54") (pinfunction "VCCIO4_54") (pintype "power_in"))
      (node (ref "U1") (pin "66") (pinfunction "VCCIO4_66") (pintype "power_in"))
      (node (ref "U1") (pin "77") (pinfunction "VCCIO3_77") (pintype "power_in"))
      (node (ref "U1") (pin "95") (pinfunction "VCCIO3_95") (pintype "power_in"))
      (node (ref "U10") (pin "3") (pinfunction "VCC_3") (pintype "power_in"))
      (node (ref "U10") (pin "7") (pinfunction "VCC_7") (pintype "power_in"))
      (node (ref "U10") (pin "8") (pinfunction "VCC_8") (pintype "power_in"))
      (node (ref "U2") (pin "5") (pinfunction "VCC_5") (pintype "power_in"))
      (node (ref "U6") (pin "5") (pinfunction "VCC_5") (pintype "power_in"))
      (node (ref "U7") (pin "1") (pinfunction "VCCA_1") (pintype "power_in"))
      (node (ref "U8") (pin "5") (pinfunction "VCC_5") (pintype "power_in"))
      (node (ref "U9") (pin "5") (pinfunction "VCC_5") (pintype "power_in"))
      (node (ref "VR1") (pin "2") (pinfunction "VOUT_2") (pintype "power_in"))
      (node (ref "VR2") (pin "3") (pinfunction "VIN_3") (pintype "bidirectional"))
      (node (ref "X1") (pin "4") (pinfunction "S_4") (pintype "passive"))
      (node (ref "XO2") (pin "4") (pinfunction "VDD_4") (pintype "power_in"))
    )
    (net (code "159") (name "unconnected-(HEADER-AUX1-Pad1)") (class "Default")
      (node (ref "HEADER") (pin "1") (pinfunction "AUX1_1") (pintype "bidirectional"))
    )
    (net (code "160") (name "unconnected-(HEADER-AUX2-Pad2)") (class "Default")
      (node (ref "HEADER") (pin "2") (pinfunction "AUX2_2") (pintype "bidirectional"))
    )
    (net (code "161") (name "unconnected-(U1-CLK3-Pad22)") (class "Default")
      (node (ref "U1") (pin "22") (pinfunction "CLK3_22") (pintype "input"))
    )
    (net (code "162") (name "unconnected-(U1-CLK4-Pad91)") (class "Default")
      (node (ref "U1") (pin "91") (pinfunction "CLK4_91") (pintype "input"))
    )
    (net (code "163") (name "unconnected-(U1-CLK5-Pad90)") (class "Default")
      (node (ref "U1") (pin "90") (pinfunction "CLK5_90") (pintype "input"))
    )
    (net (code "164") (name "unconnected-(U1-CLK6-Pad89)") (class "Default")
      (node (ref "U1") (pin "89") (pinfunction "CLK6_89") (pintype "input"))
    )
    (net (code "165") (name "unconnected-(U1-CLK7-Pad88)") (class "Default")
      (node (ref "U1") (pin "88") (pinfunction "CLK7_88") (pintype "input"))
    )
    (net (code "166") (name "unconnected-(U1-IO15-Pad32)") (class "Default")
      (node (ref "U1") (pin "32") (pinfunction "IO15_32") (pintype "bidirectional"))
    )
    (net (code "167") (name "unconnected-(U1-IO29-Pad58)") (class "Default")
      (node (ref "U1") (pin "58") (pinfunction "IO29_58") (pintype "bidirectional"))
    )
    (net (code "168") (name "unconnected-(U1-IO30-Pad59)") (class "Default")
      (node (ref "U1") (pin "59") (pinfunction "IO30_59") (pintype "bidirectional"))
    )
    (net (code "169") (name "unconnected-(U1-IO31-Pad60)") (class "Default")
      (node (ref "U1") (pin "60") (pinfunction "IO31_60") (pintype "bidirectional"))
    )
    (net (code "170") (name "unconnected-(U1-IO32-Pad63)") (class "Default")
      (node (ref "U1") (pin "63") (pinfunction "IO32_63") (pintype "bidirectional"))
    )
    (net (code "171") (name "unconnected-(U1-IO33-Pad64)") (class "Default")
      (node (ref "U1") (pin "64") (pinfunction "IO33_64") (pintype "bidirectional"))
    )
    (net (code "172") (name "unconnected-(U1-IO34-Pad65)") (class "Default")
      (node (ref "U1") (pin "65") (pinfunction "IO34_65") (pintype "bidirectional"))
    )
    (net (code "173") (name "unconnected-(U1-IO35-Pad67)") (class "Default")
      (node (ref "U1") (pin "67") (pinfunction "IO35_67") (pintype "bidirectional"))
    )
    (net (code "174") (name "unconnected-(U1-IO36-Pad69)") (class "Default")
      (node (ref "U1") (pin "69") (pinfunction "IO36_69") (pintype "bidirectional"))
    )
    (net (code "175") (name "unconnected-(U1-IO37-Pad70)") (class "Default")
      (node (ref "U1") (pin "70") (pinfunction "IO37_70") (pintype "bidirectional"))
    )
    (net (code "176") (name "unconnected-(U1-IO38-Pad71)") (class "Default")
      (node (ref "U1") (pin "71") (pinfunction "IO38_71") (pintype "bidirectional"))
    )
    (net (code "177") (name "unconnected-(U1-IO39-Pad72)") (class "Default")
      (node (ref "U1") (pin "72") (pinfunction "IO39_72") (pintype "bidirectional"))
    )
    (net (code "178") (name "unconnected-(U1-IO40-Pad73)") (class "Default")
      (node (ref "U1") (pin "73") (pinfunction "IO40_73") (pintype "bidirectional"))
    )
    (net (code "179") (name "unconnected-(U1-IO41-Pad74)") (class "Default")
      (node (ref "U1") (pin "74") (pinfunction "IO41_74") (pintype "bidirectional"))
    )
    (net (code "180") (name "unconnected-(U1-IO44-Pad79)") (class "Default")
      (node (ref "U1") (pin "79") (pinfunction "IO44_79") (pintype "bidirectional"))
    )
    (net (code "181") (name "unconnected-(U1-IO48-Pad87)") (class "Default")
      (node (ref "U1") (pin "87") (pinfunction "IO48_87") (pintype "bidirectional"))
    )
    (net (code "182") (name "unconnected-(U1-IO49-Pad92)") (class "Default")
      (node (ref "U1") (pin "92") (pinfunction "IO49_92") (pintype "bidirectional"))
    )
    (net (code "183") (name "unconnected-(U1-IO50-Pad93)") (class "Default")
      (node (ref "U1") (pin "93") (pinfunction "IO50_93") (pintype "bidirectional"))
    )
    (net (code "184") (name "unconnected-(U1-IO51-Pad94)") (class "Default")
      (node (ref "U1") (pin "94") (pinfunction "IO51_94") (pintype "bidirectional"))
    )
    (net (code "185") (name "unconnected-(U1-IO52-Pad96)") (class "Default")
      (node (ref "U1") (pin "96") (pinfunction "IO52_96") (pintype "bidirectional"))
    )
    (net (code "186") (name "unconnected-(U1-IO53-Pad97)") (class "Default")
      (node (ref "U1") (pin "97") (pinfunction "IO53_97") (pintype "bidirectional"))
    )
    (net (code "187") (name "unconnected-(U5-Y1-Pad18)") (class "Default")
      (node (ref "U5") (pin "18") (pinfunction "Y1_18") (pintype "output"))
    )
    (net (code "188") (name "unconnected-(U9-N.C-Pad1)") (class "Default")
      (node (ref "U9") (pin "1") (pinfunction "N.C_1") (pintype "no_connect"))
    )
    (net (code "189") (name "unconnected-(X1G-S-Pad6)") (class "Default")
      (node (ref "X1") (pin "6") (pinfunction "S_6") (pintype "passive"))
    )
    (net (code "190") (name "unconnected-(X1H-S-Pad7)") (class "Default")
      (node (ref "X1") (pin "7") (pinfunction "S_7") (pintype "passive"))
    )
    (net (code "191") (name "unconnected-(X1I-S-Pad8)") (class "Default")
      (node (ref "X1") (pin "8") (pinfunction "S_8") (pintype "passive"))
    )
    (net (code "192") (name "unconnected-(XO1-TS-Pad1)") (class "Default")
      (node (ref "XO1") (pin "1") (pinfunction "TS_1") (pintype "passive"))
    )
    (net (code "193") (name "unconnected-(XO2-TS-Pad1)") (class "Default")
      (node (ref "XO2") (pin "1") (pinfunction "TS_1") (pintype "passive"))
    )
  )
)
